# elasticNode.net
KiCad netlist of a schematic drawn in EAGLE
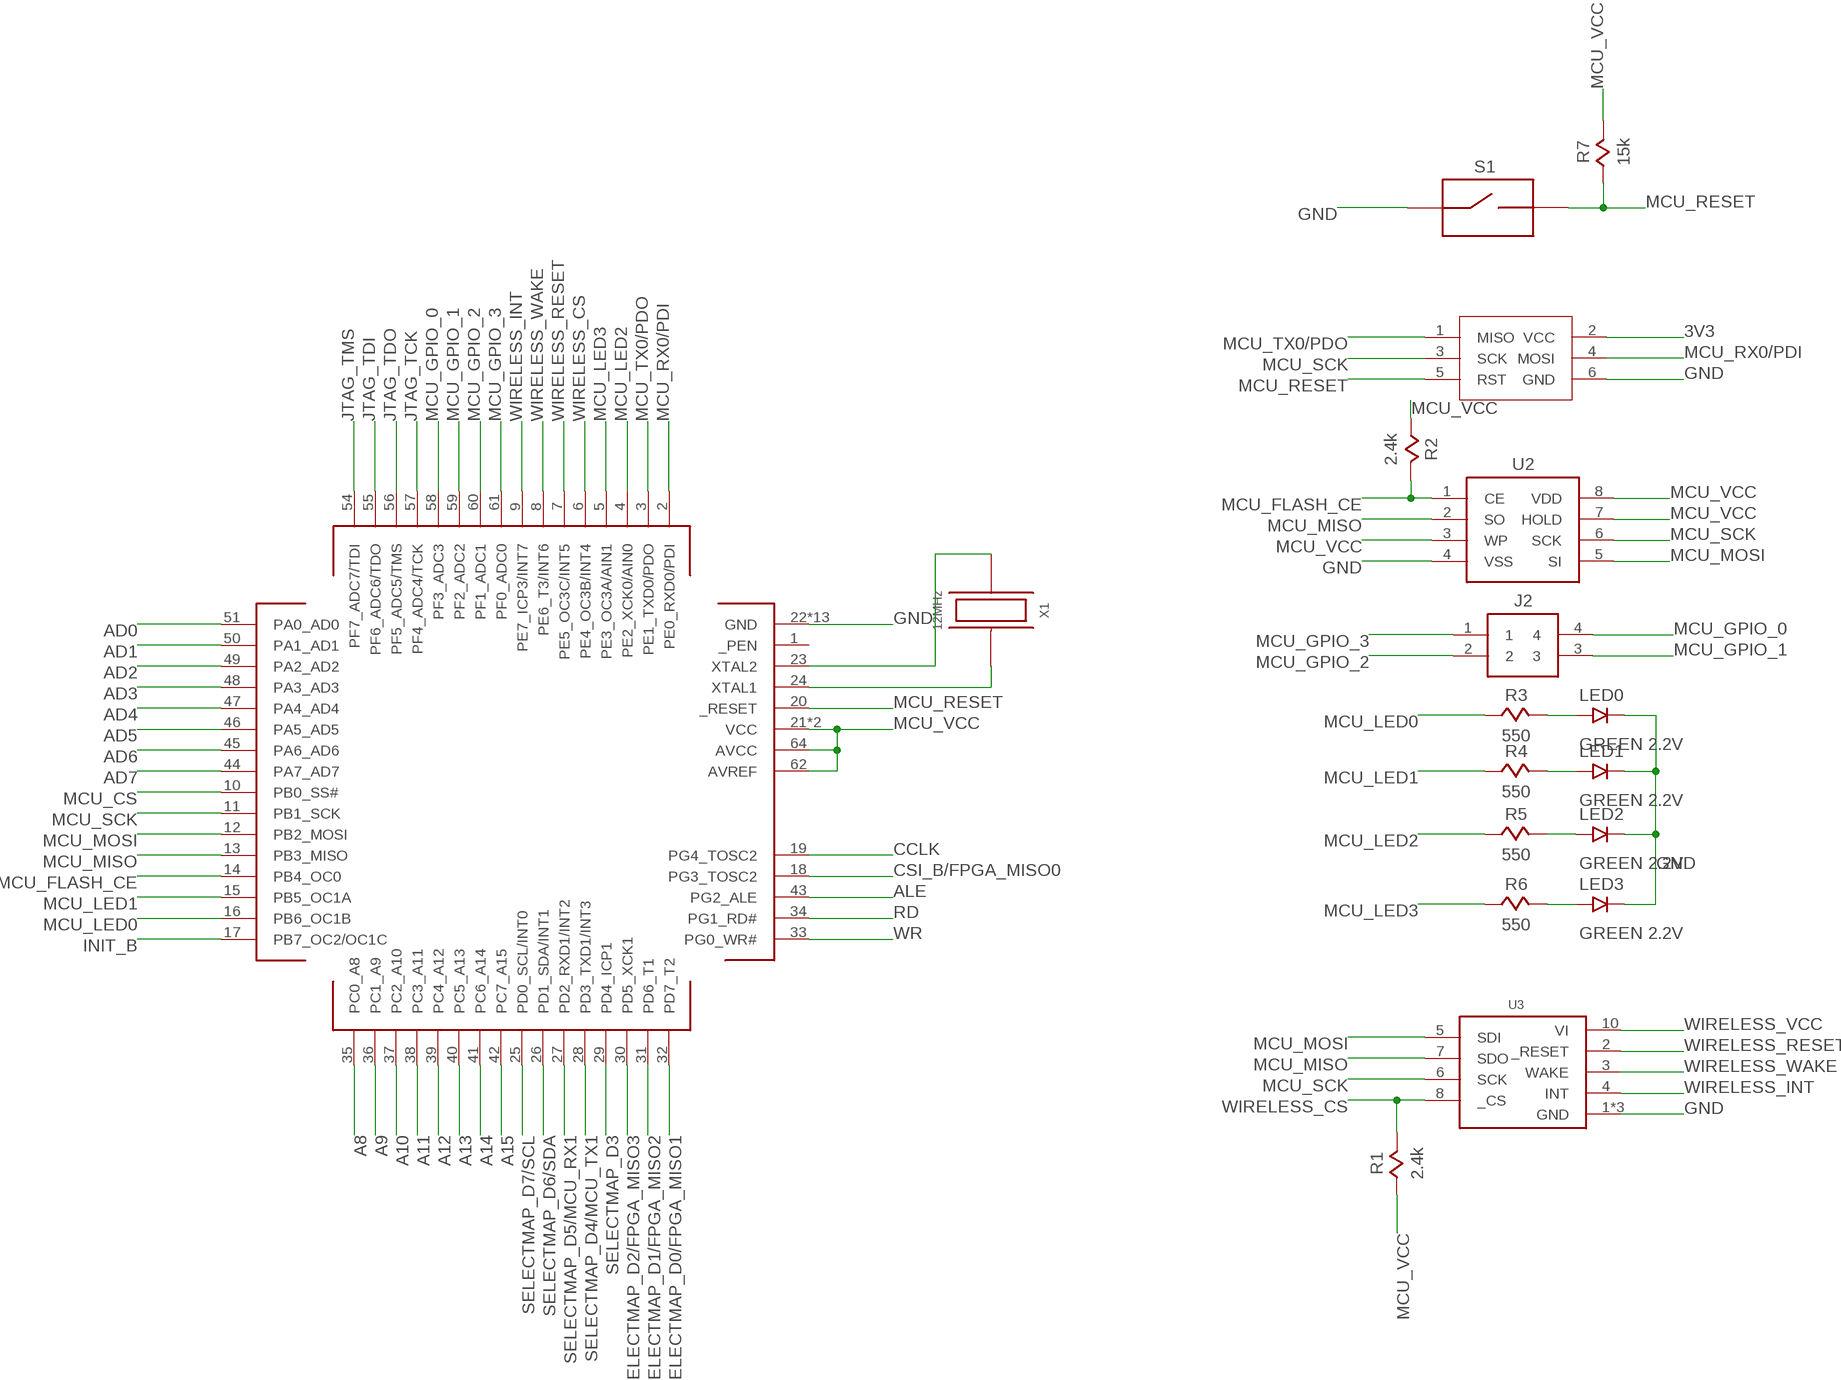
[diagram p0: schematic, sheet 1]
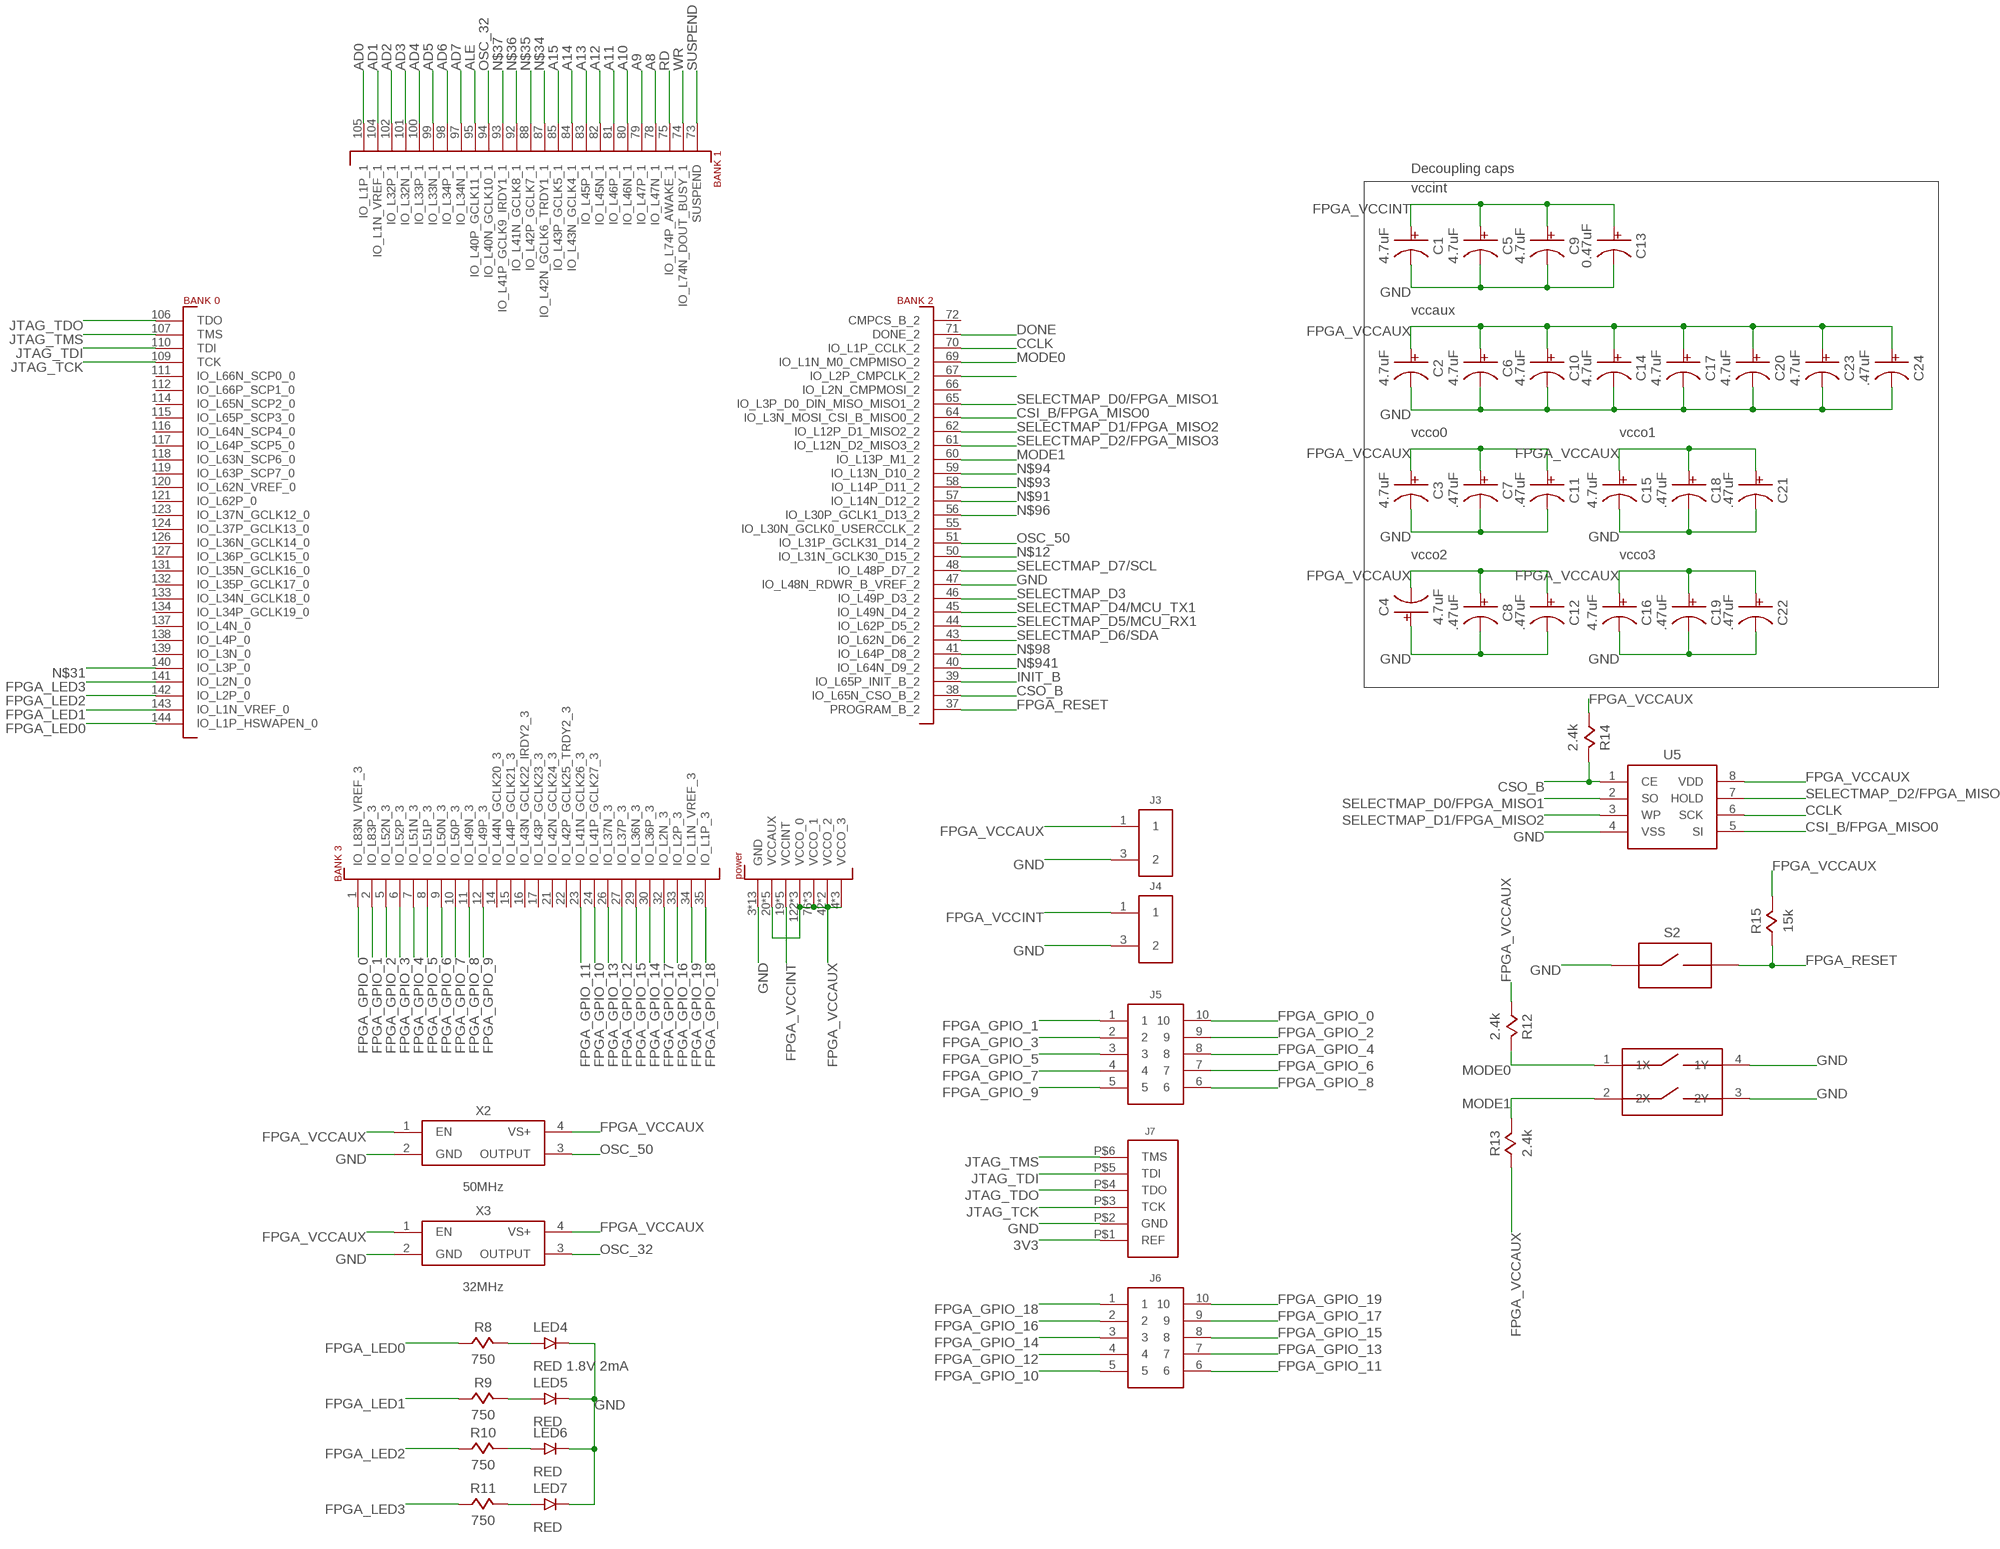
[diagram p1: schematic, sheet 2]
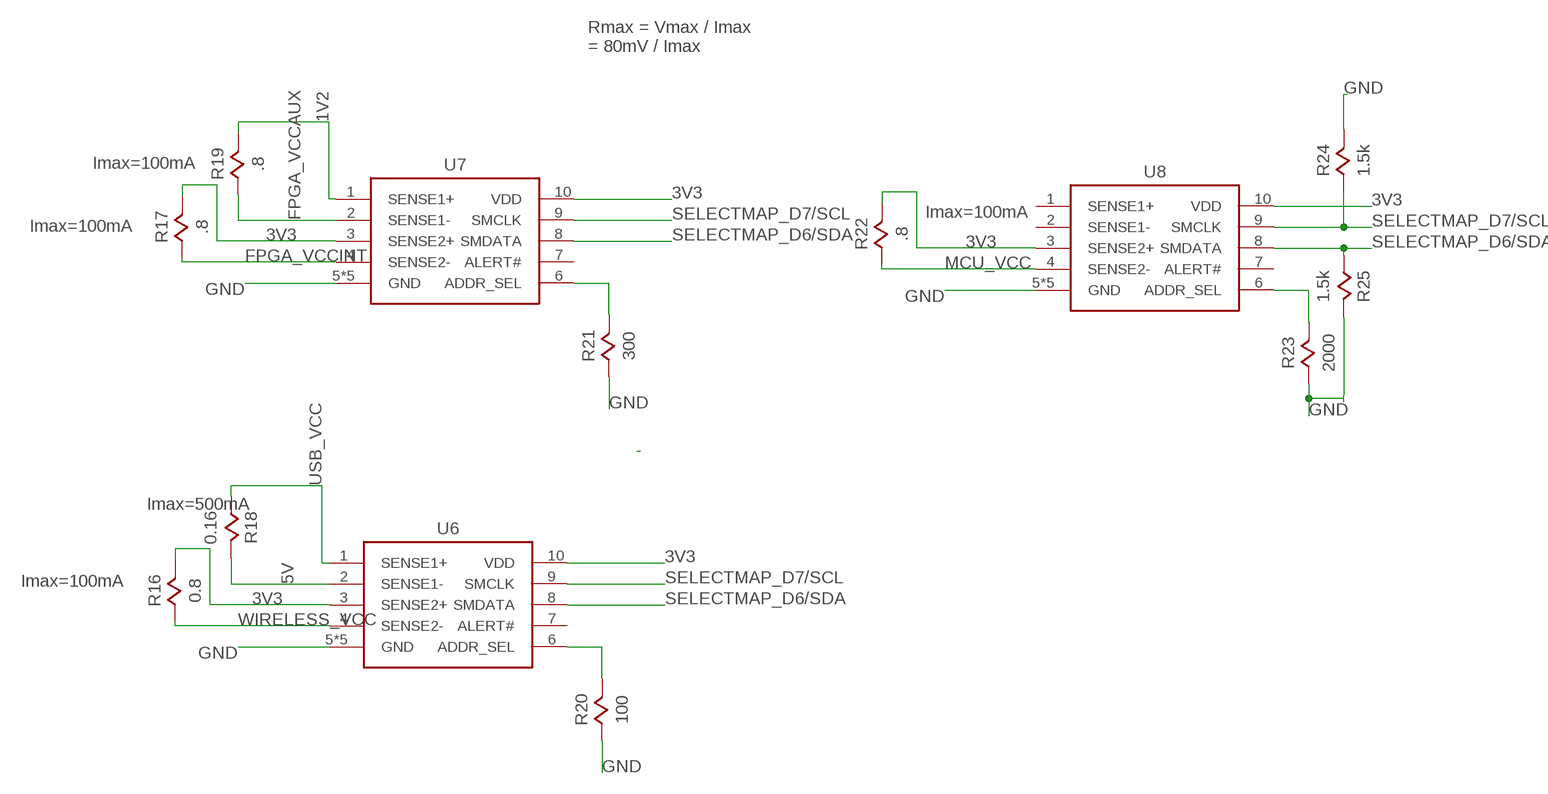
[diagram p2: schematic, sheet 3]
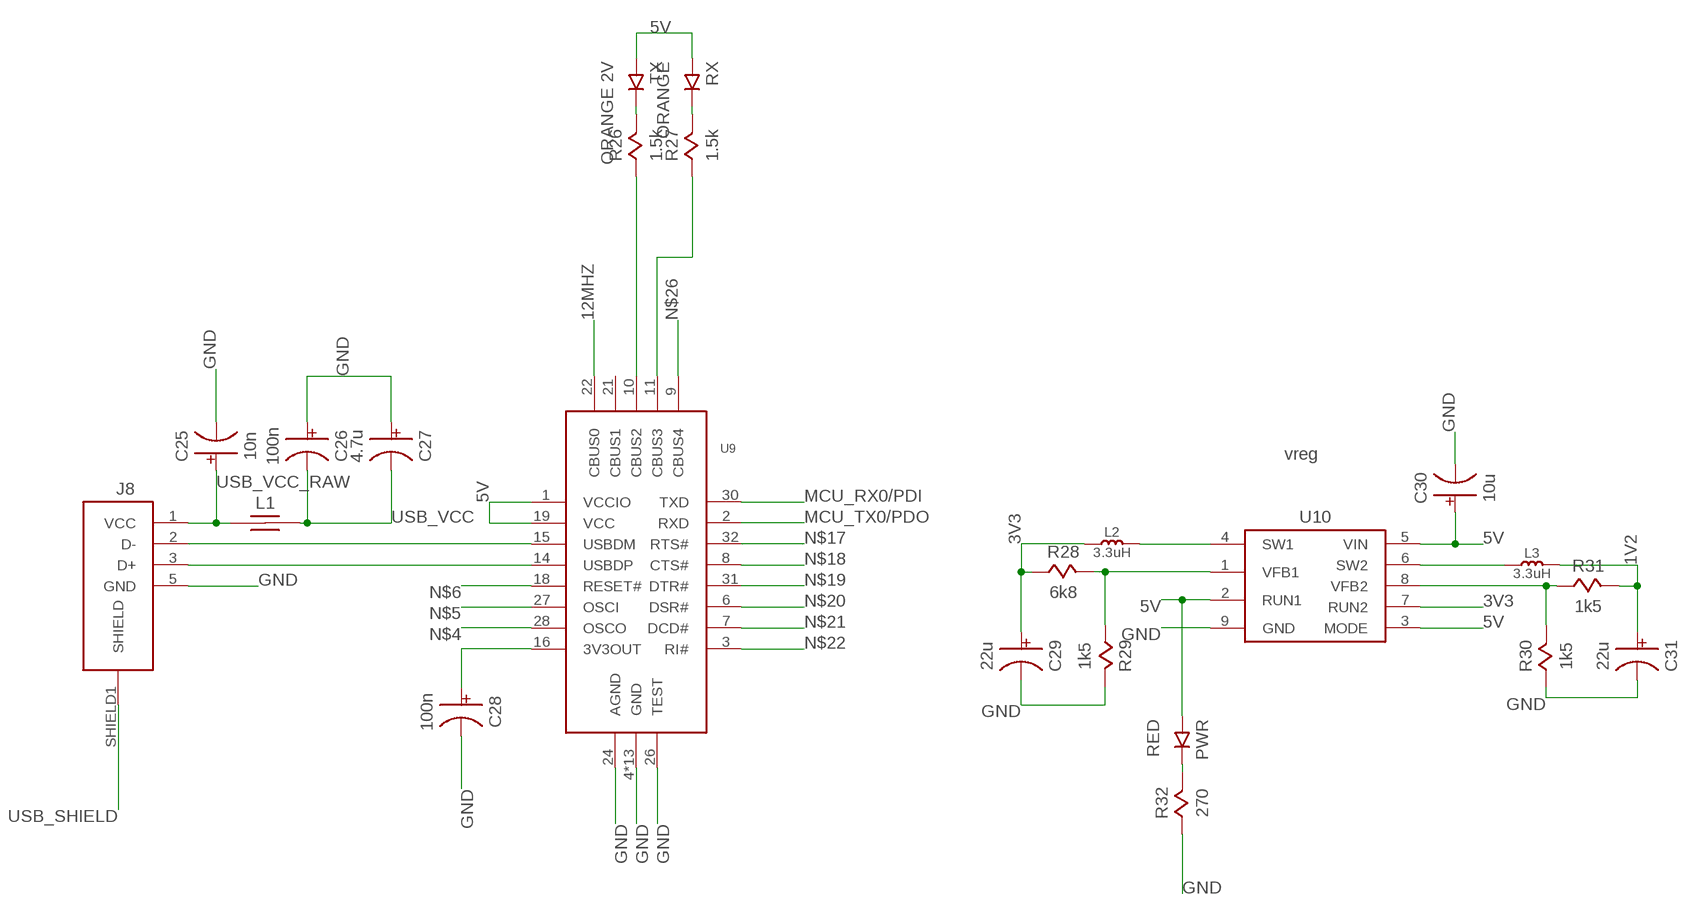
[diagram p3: schematic, sheet 4]

(export (version "E")
  (design (tool "Eeschema 10.0.6"))
  (components
    (comp (ref "C1")
      (value "4.7uF")
      (footprint "eagle-import:0805")
      (libsource (lib "eagle-import") (part "CAPACITOR0805"))
    )
    (comp (ref "C2")
      (value "4.7uF")
      (footprint "eagle-import:0805")
      (libsource (lib "eagle-import") (part "CAPACITOR0805"))
    )
    (comp (ref "C3")
      (value "4.7uF")
      (footprint "eagle-import:0805")
      (libsource (lib "eagle-import") (part "CAPACITOR0805"))
    )
    (comp (ref "C4")
      (value "4.7uF")
      (footprint "eagle-import:0805")
      (libsource (lib "eagle-import") (part "CAPACITOR0805"))
    )
    (comp (ref "C5")
      (value "4.7uF")
      (footprint "eagle-import:0805")
      (libsource (lib "eagle-import") (part "CAPACITOR0805"))
    )
    (comp (ref "C6")
      (value "4.7uF")
      (footprint "eagle-import:0805")
      (libsource (lib "eagle-import") (part "CAPACITOR0805"))
    )
    (comp (ref "C7")
      (value ".47uF")
      (footprint "eagle-import:0402")
      (libsource (lib "eagle-import") (part "CAPACITOR0402"))
    )
    (comp (ref "C8")
      (value ".47uF")
      (footprint "eagle-import:0402")
      (libsource (lib "eagle-import") (part "CAPACITOR0402"))
    )
    (comp (ref "C9")
      (value "4.7uF")
      (footprint "eagle-import:0805")
      (libsource (lib "eagle-import") (part "CAPACITOR0805"))
    )
    (comp (ref "C10")
      (value "4.7uF")
      (footprint "eagle-import:0805")
      (libsource (lib "eagle-import") (part "CAPACITOR0805"))
    )
    (comp (ref "C11")
      (value ".47uF")
      (footprint "eagle-import:0402")
      (libsource (lib "eagle-import") (part "CAPACITOR0402"))
    )
    (comp (ref "C12")
      (value ".47uF")
      (footprint "eagle-import:0402")
      (libsource (lib "eagle-import") (part "CAPACITOR0402"))
    )
    (comp (ref "C13")
      (value "0.47uF")
      (footprint "eagle-import:0402")
      (libsource (lib "eagle-import") (part "CAPACITOR0402"))
    )
    (comp (ref "C14")
      (value "4.7uF")
      (footprint "eagle-import:0805")
      (libsource (lib "eagle-import") (part "CAPACITOR0805"))
    )
    (comp (ref "C15")
      (value "4.7uF")
      (footprint "eagle-import:0805")
      (libsource (lib "eagle-import") (part "CAPACITOR0805"))
    )
    (comp (ref "C16")
      (value "4.7uF")
      (footprint "eagle-import:0805")
      (libsource (lib "eagle-import") (part "CAPACITOR0805"))
    )
    (comp (ref "C17")
      (value "4.7uF")
      (footprint "eagle-import:0805")
      (libsource (lib "eagle-import") (part "CAPACITOR0805"))
    )
    (comp (ref "C18")
      (value ".47uF")
      (footprint "eagle-import:0402")
      (libsource (lib "eagle-import") (part "CAPACITOR0402"))
    )
    (comp (ref "C19")
      (value ".47uF")
      (footprint "eagle-import:0402")
      (libsource (lib "eagle-import") (part "CAPACITOR0402"))
    )
    (comp (ref "C20")
      (value "4.7uF")
      (footprint "eagle-import:0805")
      (libsource (lib "eagle-import") (part "CAPACITOR0805"))
    )
    (comp (ref "C21")
      (value ".47uF")
      (footprint "eagle-import:0402")
      (libsource (lib "eagle-import") (part "CAPACITOR0402"))
    )
    (comp (ref "C22")
      (value ".47uF")
      (footprint "eagle-import:0402")
      (libsource (lib "eagle-import") (part "CAPACITOR0402"))
    )
    (comp (ref "C23")
      (value "4.7uF")
      (footprint "eagle-import:0805")
      (libsource (lib "eagle-import") (part "CAPACITOR0805"))
    )
    (comp (ref "C24")
      (value ".47uF")
      (footprint "eagle-import:0805")
      (libsource (lib "eagle-import") (part "CAPACITOR0805"))
    )
    (comp (ref "J3")
      (value "FEMALE_HEADER_2X1")
      (footprint "eagle-import:2X1_HEADER")
      (libsource (lib "eagle-import") (part "FEMALE_HEADER_2X1"))
    )
    (comp (ref "J4")
      (value "FEMALE_HEADER_2X1")
      (footprint "eagle-import:2X1_HEADER")
      (libsource (lib "eagle-import") (part "FEMALE_HEADER_2X1"))
    )
    (comp (ref "J5")
      (value "FEMALE_HEADER_5X2")
      (footprint "eagle-import:5X2_HEADER")
      (libsource (lib "eagle-import") (part "FEMALE_HEADER_5X2"))
    )
    (comp (ref "J6")
      (value "FEMALE_HEADER_5X2")
      (footprint "eagle-import:5X2_HEADER")
      (libsource (lib "eagle-import") (part "FEMALE_HEADER_5X2"))
    )
    (comp (ref "J7")
      (value "JTAG_CONN_6PINTHT")
      (footprint "eagle-import:6X1_HEADER")
      (libsource (lib "eagle-import") (part "JTAG_CONN_6PINTHT"))
    )
    (comp (ref "LED4")
      (value "RED 1.8V 2mA")
      (footprint "eagle-import:0805")
      (libsource (lib "eagle-import") (part "LED"))
    )
    (comp (ref "LED5")
      (value "RED")
      (footprint "eagle-import:0805")
      (libsource (lib "eagle-import") (part "LED"))
    )
    (comp (ref "LED6")
      (value "RED")
      (footprint "eagle-import:0805")
      (libsource (lib "eagle-import") (part "LED"))
    )
    (comp (ref "LED7")
      (value "RED")
      (footprint "eagle-import:0805")
      (libsource (lib "eagle-import") (part "LED"))
    )
    (comp (ref "R8")
      (value "750")
      (footprint "eagle-import:0805")
      (libsource (lib "eagle-import") (part "RESISTOR"))
    )
    (comp (ref "R9")
      (value "750")
      (footprint "eagle-import:0805")
      (libsource (lib "eagle-import") (part "RESISTOR"))
    )
    (comp (ref "R10")
      (value "750")
      (footprint "eagle-import:0805")
      (libsource (lib "eagle-import") (part "RESISTOR"))
    )
    (comp (ref "R11")
      (value "750")
      (footprint "eagle-import:0805")
      (libsource (lib "eagle-import") (part "RESISTOR"))
    )
    (comp (ref "R12")
      (value "2.4k")
      (footprint "eagle-import:0805")
      (libsource (lib "eagle-import") (part "RESISTOR"))
    )
    (comp (ref "R13")
      (value "2.4k")
      (footprint "eagle-import:0805")
      (libsource (lib "eagle-import") (part "RESISTOR"))
    )
    (comp (ref "R14")
      (value "2.4k")
      (footprint "eagle-import:0805")
      (libsource (lib "eagle-import") (part "RESISTOR"))
    )
    (comp (ref "R15")
      (value "15k")
      (footprint "eagle-import:0805")
      (libsource (lib "eagle-import") (part "RESISTOR"))
    )
    (comp (ref "S2")
      (value "SPST_BUTTON2PIN_SMT")
      (footprint "eagle-import:SPST_2PIN_SMT")
      (libsource (lib "eagle-import") (part "SPST_BUTTON2PIN_SMT"))
    )
    (comp (ref "S3")
      (value "SPST_DIP_2SMT")
      (footprint "eagle-import:SPST_DIP2_SMT")
      (libsource (lib "eagle-import") (part "SPST_DIP_2SMT"))
    )
    (comp (ref "U4")
      (value "SPARTAN6-LX9")
      (footprint "eagle-import:TQG144")
      (libsource (lib "eagle-import") (part "SPARTAN6-LX9"))
    )
    (comp (ref "U5")
      (value "SST26VF032B")
      (footprint "eagle-import:SOIC8")
      (libsource (lib "eagle-import") (part "SST26VF032B"))
    )
    (comp (ref "X2")
      (value "50MHz")
      (footprint "eagle-import:3.2X2.5_OSC")
      (libsource (lib "eagle-import") (part "OSCILLATOR3.2X2.5"))
    )
    (comp (ref "X3")
      (value "32MHz")
      (footprint "eagle-import:3.2X2.5_OSC")
      (libsource (lib "eagle-import") (part "OSCILLATOR3.2X2.5"))
    )
    (comp (ref "C25")
      (value "10n")
      (footprint "eagle-import:0805")
      (libsource (lib "eagle-import") (part "CAPACITOR0805"))
    )
    (comp (ref "C26")
      (value "100n")
      (footprint "eagle-import:0805")
      (libsource (lib "eagle-import") (part "CAPACITOR0805"))
    )
    (comp (ref "C27")
      (value "4.7u")
      (footprint "eagle-import:0805")
      (libsource (lib "eagle-import") (part "CAPACITOR0805"))
    )
    (comp (ref "C28")
      (value "100n")
      (footprint "eagle-import:0805")
      (libsource (lib "eagle-import") (part "CAPACITOR0805"))
    )
    (comp (ref "C29")
      (value "22u")
      (footprint "eagle-import:0805")
      (libsource (lib "eagle-import") (part "CAPACITOR0805"))
    )
    (comp (ref "C30")
      (value "10u")
      (footprint "eagle-import:0805")
      (libsource (lib "eagle-import") (part "CAPACITOR0805"))
    )
    (comp (ref "C31")
      (value "22u")
      (footprint "eagle-import:0805")
      (libsource (lib "eagle-import") (part "CAPACITOR0805"))
    )
    (comp (ref "J8")
      (value "USB_CONN")
      (footprint "eagle-import:USB_MICRO_B")
      (libsource (lib "eagle-import") (part "USB_CONN"))
    )
    (comp (ref "L1")
      (value "40Ohm 1.5A")
      (footprint "eagle-import:0805")
      (libsource (lib "eagle-import") (part "FERRITE_BEAD"))
    )
    (comp (ref "L2")
      (value "3.3uH")
      (footprint "eagle-import:0805")
      (libsource (lib "eagle-import") (part "INDUCTOR"))
    )
    (comp (ref "L3")
      (value "3.3uH")
      (footprint "eagle-import:0805")
      (libsource (lib "eagle-import") (part "INDUCTOR"))
    )
    (comp (ref "PWR")
      (value "RED")
      (footprint "eagle-import:0805")
      (libsource (lib "eagle-import") (part "LED"))
    )
    (comp (ref "R26")
      (value "1.5k")
      (footprint "eagle-import:0805")
      (libsource (lib "eagle-import") (part "RESISTOR"))
    )
    (comp (ref "R27")
      (value "1.5k")
      (footprint "eagle-import:0805")
      (libsource (lib "eagle-import") (part "RESISTOR"))
    )
    (comp (ref "R28")
      (value "6k8")
      (footprint "eagle-import:0805")
      (libsource (lib "eagle-import") (part "RESISTOR"))
    )
    (comp (ref "R29")
      (value "1k5")
      (footprint "eagle-import:0805")
      (libsource (lib "eagle-import") (part "RESISTOR"))
    )
    (comp (ref "R30")
      (value "1k5")
      (footprint "eagle-import:0805")
      (libsource (lib "eagle-import") (part "RESISTOR"))
    )
    (comp (ref "R31")
      (value "1k5")
      (footprint "eagle-import:0805")
      (libsource (lib "eagle-import") (part "RESISTOR"))
    )
    (comp (ref "R32")
      (value "270")
      (footprint "eagle-import:0805")
      (libsource (lib "eagle-import") (part "RESISTOR"))
    )
    (comp (ref "RX")
      (value "ORANGE")
      (footprint "eagle-import:0805")
      (libsource (lib "eagle-import") (part "LED"))
    )
    (comp (ref "TX")
      (value "ORANGE 2V")
      (footprint "eagle-import:0805")
      (libsource (lib "eagle-import") (part "LED"))
    )
    (comp (ref "U9")
      (value "FT232R")
      (footprint "eagle-import:QFN32")
      (libsource (lib "eagle-import") (part "FT232R"))
    )
    (comp (ref "U10")
      (value "LTC3419DFN")
      (footprint "eagle-import:DFN8")
      (libsource (lib "eagle-import") (part "LTC3419DFN"))
    )
    (comp (ref "R16")
      (value "0.8")
      (footprint "eagle-import:0805")
      (libsource (lib "eagle-import") (part "RESISTOR"))
    )
    (comp (ref "R17")
      (value ".8")
      (footprint "eagle-import:0805")
      (libsource (lib "eagle-import") (part "RESISTOR"))
    )
    (comp (ref "R18")
      (value "0.16")
      (footprint "eagle-import:0805")
      (libsource (lib "eagle-import") (part "RESISTOR"))
    )
    (comp (ref "R19")
      (value ".8")
      (footprint "eagle-import:0805")
      (libsource (lib "eagle-import") (part "RESISTOR"))
    )
    (comp (ref "R20")
      (value "100")
      (footprint "eagle-import:0805")
      (libsource (lib "eagle-import") (part "RESISTOR"))
    )
    (comp (ref "R21")
      (value "300")
      (footprint "eagle-import:0805")
      (libsource (lib "eagle-import") (part "RESISTOR"))
    )
    (comp (ref "R22")
      (value ".8")
      (footprint "eagle-import:0805")
      (libsource (lib "eagle-import") (part "RESISTOR"))
    )
    (comp (ref "R23")
      (value "2000")
      (footprint "eagle-import:0805")
      (libsource (lib "eagle-import") (part "RESISTOR"))
    )
    (comp (ref "R24")
      (value "1.5k")
      (footprint "eagle-import:0805")
      (libsource (lib "eagle-import") (part "RESISTOR"))
    )
    (comp (ref "R25")
      (value "1.5k")
      (footprint "eagle-import:0805")
      (libsource (lib "eagle-import") (part "RESISTOR"))
    )
    (comp (ref "U6")
      (value "PAC1720")
      (footprint "eagle-import:VDFN10")
      (libsource (lib "eagle-import") (part "PAC1720"))
    )
    (comp (ref "U7")
      (value "PAC1720")
      (footprint "eagle-import:VDFN10")
      (libsource (lib "eagle-import") (part "PAC1720"))
    )
    (comp (ref "U8")
      (value "PAC1720")
      (footprint "eagle-import:VDFN10")
      (libsource (lib "eagle-import") (part "PAC1720"))
    )
    (comp (ref "J1")
      (value "ISP_CONN_6PIN")
      (footprint "eagle-import:3X2_HEADER_SMT")
      (libsource (lib "eagle-import") (part "ISP_CONN_6PIN"))
    )
    (comp (ref "J2")
      (value "FEMALE_HEADER_2X2")
      (footprint "eagle-import:2X2_HEADER")
      (libsource (lib "eagle-import") (part "FEMALE_HEADER_2X2"))
    )
    (comp (ref "LED0")
      (value "GREEN 2.2V")
      (footprint "eagle-import:0805")
      (libsource (lib "eagle-import") (part "LED"))
    )
    (comp (ref "LED1")
      (value "GREEN 2.2V")
      (footprint "eagle-import:0805")
      (libsource (lib "eagle-import") (part "LED"))
    )
    (comp (ref "LED2")
      (value "GREEN 2.2V")
      (footprint "eagle-import:0805")
      (libsource (lib "eagle-import") (part "LED"))
    )
    (comp (ref "LED3")
      (value "GREEN 2.2V")
      (footprint "eagle-import:0805")
      (libsource (lib "eagle-import") (part "LED"))
    )
    (comp (ref "R1")
      (value "2.4k")
      (footprint "eagle-import:0805")
      (libsource (lib "eagle-import") (part "RESISTOR"))
    )
    (comp (ref "R2")
      (value "2.4k")
      (footprint "eagle-import:0805")
      (libsource (lib "eagle-import") (part "RESISTOR"))
    )
    (comp (ref "R3")
      (value "550")
      (footprint "eagle-import:0805")
      (libsource (lib "eagle-import") (part "RESISTOR"))
    )
    (comp (ref "R4")
      (value "550")
      (footprint "eagle-import:0805")
      (libsource (lib "eagle-import") (part "RESISTOR"))
    )
    (comp (ref "R5")
      (value "550")
      (footprint "eagle-import:0805")
      (libsource (lib "eagle-import") (part "RESISTOR"))
    )
    (comp (ref "R6")
      (value "550")
      (footprint "eagle-import:0805")
      (libsource (lib "eagle-import") (part "RESISTOR"))
    )
    (comp (ref "R7")
      (value "15k")
      (footprint "eagle-import:0805")
      (libsource (lib "eagle-import") (part "RESISTOR"))
    )
    (comp (ref "S1")
      (value "SPST_BUTTON2PIN_SMT")
      (footprint "eagle-import:SPST_2PIN_SMT")
      (libsource (lib "eagle-import") (part "SPST_BUTTON2PIN_SMT"))
    )
    (comp (ref "U1")
      (value "ATMEGA64AQFN")
      (footprint "eagle-import:QFN64")
      (libsource (lib "eagle-import") (part "ATMEGA64AQFN"))
    )
    (comp (ref "U2")
      (value "SST26VF032B")
      (footprint "eagle-import:SOIC8")
      (libsource (lib "eagle-import") (part "SST26VF032B"))
    )
    (comp (ref "U3")
      (value "MRF24J40MA")
      (footprint "eagle-import:MRF24J40MA")
      (libsource (lib "eagle-import") (part "MRF24J40MA"))
    )
    (comp (ref "X1")
      (value "12MHz")
      (footprint "eagle-import:3.2X2.5_OSC")
      (libsource (lib "eagle-import") (part "QUARTZ"))
    )
  )
  (nets
    (net (code "1") (name "1V2") (class "Default")
      (node (ref "C31") (pin "1") (pinfunction "P$1_1") (pintype "bidirectional"))
      (node (ref "L3") (pin "2") (pinfunction "P$2_2") (pintype "bidirectional"))
      (node (ref "R19") (pin "2") (pinfunction "2_2") (pintype "bidirectional"))
      (node (ref "R31") (pin "2") (pinfunction "2_2") (pintype "bidirectional"))
      (node (ref "U7") (pin "1") (pinfunction "SENSE1+_1") (pintype "bidirectional"))
    )
    (net (code "2") (name "3V3") (class "Default")
      (node (ref "C29") (pin "1") (pinfunction "P$1_1") (pintype "bidirectional"))
      (node (ref "J1") (pin "2") (pinfunction "VCC_2") (pintype "bidirectional"))
      (node (ref "J7") (pin "P$1") (pinfunction "REF_P$1") (pintype "bidirectional"))
      (node (ref "L2") (pin "1") (pinfunction "P$1_1") (pintype "bidirectional"))
      (node (ref "R16") (pin "2") (pinfunction "2_2") (pintype "bidirectional"))
      (node (ref "R17") (pin "2") (pinfunction "2_2") (pintype "bidirectional"))
      (node (ref "R22") (pin "2") (pinfunction "2_2") (pintype "bidirectional"))
      (node (ref "R28") (pin "1") (pinfunction "1_1") (pintype "bidirectional"))
      (node (ref "U10") (pin "7") (pinfunction "RUN2_7") (pintype "bidirectional"))
      (node (ref "U6") (pin "10") (pinfunction "VDD_10") (pintype "bidirectional"))
      (node (ref "U6") (pin "3") (pinfunction "SENSE2+_3") (pintype "bidirectional"))
      (node (ref "U7") (pin "10") (pinfunction "VDD_10") (pintype "bidirectional"))
      (node (ref "U7") (pin "3") (pinfunction "SENSE2+_3") (pintype "bidirectional"))
      (node (ref "U8") (pin "10") (pinfunction "VDD_10") (pintype "bidirectional"))
      (node (ref "U8") (pin "3") (pinfunction "SENSE2+_3") (pintype "bidirectional"))
    )
    (net (code "3") (name "5V") (class "Default")
      (node (ref "C30") (pin "1") (pinfunction "P$1_1") (pintype "bidirectional"))
      (node (ref "PWR") (pin "1") (pinfunction "1_1") (pintype "bidirectional"))
      (node (ref "R18") (pin "2") (pinfunction "2_2") (pintype "bidirectional"))
      (node (ref "RX") (pin "1") (pinfunction "1_1") (pintype "bidirectional"))
      (node (ref "TX") (pin "1") (pinfunction "1_1") (pintype "bidirectional"))
      (node (ref "U10") (pin "2") (pinfunction "RUN1_2") (pintype "bidirectional"))
      (node (ref "U10") (pin "3") (pinfunction "MODE_3") (pintype "bidirectional"))
      (node (ref "U10") (pin "5") (pinfunction "VIN_5") (pintype "bidirectional"))
      (node (ref "U6") (pin "2") (pinfunction "SENSE1-_2") (pintype "bidirectional"))
      (node (ref "U9") (pin "1") (pinfunction "VCCIO_1") (pintype "bidirectional"))
      (node (ref "U9") (pin "19") (pinfunction "VCC_19") (pintype "bidirectional"))
    )
    (net (code "4") (name "12MHZ") (class "Default")
      (node (ref "U9") (pin "22") (pinfunction "CBUS0_22") (pintype "bidirectional"))
    )
    (net (code "5") (name "A8") (class "Default")
      (node (ref "U1") (pin "35") (pinfunction "PC0_A8_35") (pintype "bidirectional"))
      (node (ref "U4") (pin "78") (pinfunction "IO_L47N_1_78") (pintype "bidirectional"))
    )
    (net (code "6") (name "A9") (class "Default")
      (node (ref "U1") (pin "36") (pinfunction "PC1_A9_36") (pintype "bidirectional"))
      (node (ref "U4") (pin "79") (pinfunction "IO_L47P_1_79") (pintype "bidirectional"))
    )
    (net (code "7") (name "A10") (class "Default")
      (node (ref "U1") (pin "37") (pinfunction "PC2_A10_37") (pintype "bidirectional"))
      (node (ref "U4") (pin "80") (pinfunction "IO_L46N_1_80") (pintype "bidirectional"))
    )
    (net (code "8") (name "A11") (class "Default")
      (node (ref "U1") (pin "38") (pinfunction "PC3_A11_38") (pintype "bidirectional"))
      (node (ref "U4") (pin "81") (pinfunction "IO_L46P_1_81") (pintype "bidirectional"))
    )
    (net (code "9") (name "A12") (class "Default")
      (node (ref "U1") (pin "39") (pinfunction "PC4_A12_39") (pintype "bidirectional"))
      (node (ref "U4") (pin "82") (pinfunction "IO_L45N_1_82") (pintype "bidirectional"))
    )
    (net (code "10") (name "A13") (class "Default")
      (node (ref "U1") (pin "40") (pinfunction "PC5_A13_40") (pintype "bidirectional"))
      (node (ref "U4") (pin "83") (pinfunction "IO_L45P_1_83") (pintype "bidirectional"))
    )
    (net (code "11") (name "A14") (class "Default")
      (node (ref "U1") (pin "41") (pinfunction "PC6_A14_41") (pintype "bidirectional"))
      (node (ref "U4") (pin "84") (pinfunction "IO_L43N_GCLK4_1_84") (pintype "bidirectional"))
    )
    (net (code "12") (name "A15") (class "Default")
      (node (ref "U1") (pin "42") (pinfunction "PC7_A15_42") (pintype "bidirectional"))
      (node (ref "U4") (pin "85") (pinfunction "IO_L43P_GCLK5_1_85") (pintype "bidirectional"))
    )
    (net (code "13") (name "AD0") (class "Default")
      (node (ref "U1") (pin "51") (pinfunction "PA0_AD0_51") (pintype "bidirectional"))
      (node (ref "U4") (pin "105") (pinfunction "IO_L1P_1_105") (pintype "bidirectional"))
    )
    (net (code "14") (name "AD1") (class "Default")
      (node (ref "U1") (pin "50") (pinfunction "PA1_AD1_50") (pintype "bidirectional"))
      (node (ref "U4") (pin "104") (pinfunction "IO_L1N_VREF_1_104") (pintype "bidirectional"))
    )
    (net (code "15") (name "AD2") (class "Default")
      (node (ref "U1") (pin "49") (pinfunction "PA2_AD2_49") (pintype "bidirectional"))
      (node (ref "U4") (pin "102") (pinfunction "IO_L32P_1_102") (pintype "bidirectional"))
    )
    (net (code "16") (name "AD3") (class "Default")
      (node (ref "U1") (pin "48") (pinfunction "PA3_AD3_48") (pintype "bidirectional"))
      (node (ref "U4") (pin "101") (pinfunction "IO_L32N_1_101") (pintype "bidirectional"))
    )
    (net (code "17") (name "AD4") (class "Default")
      (node (ref "U1") (pin "47") (pinfunction "PA4_AD4_47") (pintype "bidirectional"))
      (node (ref "U4") (pin "100") (pinfunction "IO_L33P_1_100") (pintype "bidirectional"))
    )
    (net (code "18") (name "AD5") (class "Default")
      (node (ref "U1") (pin "46") (pinfunction "PA5_AD5_46") (pintype "bidirectional"))
      (node (ref "U4") (pin "99") (pinfunction "IO_L33N_1_99") (pintype "bidirectional"))
    )
    (net (code "19") (name "AD6") (class "Default")
      (node (ref "U1") (pin "45") (pinfunction "PA6_AD6_45") (pintype "bidirectional"))
      (node (ref "U4") (pin "98") (pinfunction "IO_L34P_1_98") (pintype "bidirectional"))
    )
    (net (code "20") (name "AD7") (class "Default")
      (node (ref "U1") (pin "44") (pinfunction "PA7_AD7_44") (pintype "bidirectional"))
      (node (ref "U4") (pin "97") (pinfunction "IO_L34N_1_97") (pintype "bidirectional"))
    )
    (net (code "21") (name "ALE") (class "Default")
      (node (ref "U1") (pin "43") (pinfunction "PG2_ALE_43") (pintype "bidirectional"))
      (node (ref "U4") (pin "95") (pinfunction "IO_L40P_GCLK11_1_95") (pintype "bidirectional"))
    )
    (net (code "22") (name "CCLK") (class "Default")
      (node (ref "U1") (pin "19") (pinfunction "PG4_TOSC2_19") (pintype "bidirectional"))
      (node (ref "U4") (pin "70") (pinfunction "IO_L1P_CCLK_2_70") (pintype "bidirectional"))
      (node (ref "U5") (pin "6") (pinfunction "SCK_6") (pintype "bidirectional"))
    )
    (net (code "23") (name "CSI_B{slash}FPGA_MISO0") (class "Default")
      (node (ref "U1") (pin "18") (pinfunction "PG3_TOSC2_18") (pintype "bidirectional"))
      (node (ref "U4") (pin "64") (pinfunction "IO_L3N_MOSI_CSI_B_MISO0_2_64") (pintype "bidirectional"))
      (node (ref "U5") (pin "5") (pinfunction "SI_5") (pintype "bidirectional"))
    )
    (net (code "24") (name "CSO_B") (class "Default")
      (node (ref "R14") (pin "2") (pinfunction "2_2") (pintype "bidirectional"))
      (node (ref "U4") (pin "38") (pinfunction "IO_L65N_CSO_B_2_38") (pintype "bidirectional"))
      (node (ref "U5") (pin "1") (pinfunction "CE_1") (pintype "bidirectional"))
    )
    (net (code "25") (name "DONE") (class "Default")
      (node (ref "U4") (pin "71") (pinfunction "DONE_2_71") (pintype "bidirectional"))
    )
    (net (code "26") (name "FPGA_GPIO_0") (class "Default")
      (node (ref "J5") (pin "10") (pinfunction "10_10") (pintype "bidirectional"))
      (node (ref "U4") (pin "1") (pinfunction "IO_L83N_VREF_3_1") (pintype "bidirectional"))
    )
    (net (code "27") (name "FPGA_GPIO_1") (class "Default")
      (node (ref "J5") (pin "1") (pinfunction "1_1") (pintype "bidirectional"))
      (node (ref "U4") (pin "2") (pinfunction "IO_L83P_3_2") (pintype "bidirectional"))
    )
    (net (code "28") (name "FPGA_GPIO_2") (class "Default")
      (node (ref "J5") (pin "9") (pinfunction "9_9") (pintype "bidirectional"))
      (node (ref "U4") (pin "5") (pinfunction "IO_L52N_3_5") (pintype "bidirectional"))
    )
    (net (code "29") (name "FPGA_GPIO_3") (class "Default")
      (node (ref "J5") (pin "2") (pinfunction "2_2") (pintype "bidirectional"))
      (node (ref "U4") (pin "6") (pinfunction "IO_L52P_3_6") (pintype "bidirectional"))
    )
    (net (code "30") (name "FPGA_GPIO_4") (class "Default")
      (node (ref "J5") (pin "8") (pinfunction "8_8") (pintype "bidirectional"))
      (node (ref "U4") (pin "7") (pinfunction "IO_L51N_3_7") (pintype "bidirectional"))
    )
    (net (code "31") (name "FPGA_GPIO_5") (class "Default")
      (node (ref "J5") (pin "3") (pinfunction "3_3") (pintype "bidirectional"))
      (node (ref "U4") (pin "8") (pinfunction "IO_L51P_3_8") (pintype "bidirectional"))
    )
    (net (code "32") (name "FPGA_GPIO_6") (class "Default")
      (node (ref "J5") (pin "7") (pinfunction "7_7") (pintype "bidirectional"))
      (node (ref "U4") (pin "9") (pinfunction "IO_L50N_3_9") (pintype "bidirectional"))
    )
    (net (code "33") (name "FPGA_GPIO_7") (class "Default")
      (node (ref "J5") (pin "4") (pinfunction "4_4") (pintype "bidirectional"))
      (node (ref "U4") (pin "10") (pinfunction "IO_L50P_3_10") (pintype "bidirectional"))
    )
    (net (code "34") (name "FPGA_GPIO_8") (class "Default")
      (node (ref "J5") (pin "6") (pinfunction "6_6") (pintype "bidirectional"))
      (node (ref "U4") (pin "11") (pinfunction "IO_L49N_3_11") (pintype "bidirectional"))
    )
    (net (code "35") (name "FPGA_GPIO_9") (class "Default")
      (node (ref "J5") (pin "5") (pinfunction "5_5") (pintype "bidirectional"))
      (node (ref "U4") (pin "12") (pinfunction "IO_L49P_3_12") (pintype "bidirectional"))
    )
    (net (code "36") (name "FPGA_GPIO_10") (class "Default")
      (node (ref "J6") (pin "5") (pinfunction "5_5") (pintype "bidirectional"))
      (node (ref "U4") (pin "24") (pinfunction "IO_L41P_GCLK27_3_24") (pintype "bidirectional"))
    )
    (net (code "37") (name "FPGA_GPIO_11") (class "Default")
      (node (ref "J6") (pin "6") (pinfunction "6_6") (pintype "bidirectional"))
      (node (ref "U4") (pin "23") (pinfunction "IO_L41N_GCLK26_3_23") (pintype "bidirectional"))
    )
    (net (code "38") (name "FPGA_GPIO_12") (class "Default")
      (node (ref "J6") (pin "4") (pinfunction "4_4") (pintype "bidirectional"))
      (node (ref "U4") (pin "27") (pinfunction "IO_L37P_3_27") (pintype "bidirectional"))
    )
    (net (code "39") (name "FPGA_GPIO_13") (class "Default")
      (node (ref "J6") (pin "7") (pinfunction "7_7") (pintype "bidirectional"))
      (node (ref "U4") (pin "26") (pinfunction "IO_L37N_3_26") (pintype "bidirectional"))
    )
    (net (code "40") (name "FPGA_GPIO_14") (class "Default")
      (node (ref "J6") (pin "3") (pinfunction "3_3") (pintype "bidirectional"))
      (node (ref "U4") (pin "30") (pinfunction "IO_L36P_3_30") (pintype "bidirectional"))
    )
    (net (code "41") (name "FPGA_GPIO_15") (class "Default")
      (node (ref "J6") (pin "8") (pinfunction "8_8") (pintype "bidirectional"))
      (node (ref "U4") (pin "29") (pinfunction "IO_L36N_3_29") (pintype "bidirectional"))
    )
    (net (code "42") (name "FPGA_GPIO_16") (class "Default")
      (node (ref "J6") (pin "2") (pinfunction "2_2") (pintype "bidirectional"))
      (node (ref "U4") (pin "33") (pinfunction "IO_L2P_3_33") (pintype "bidirectional"))
    )
    (net (code "43") (name "FPGA_GPIO_17") (class "Default")
      (node (ref "J6") (pin "9") (pinfunction "9_9") (pintype "bidirectional"))
      (node (ref "U4") (pin "32") (pinfunction "IO_L2N_3_32") (pintype "bidirectional"))
    )
    (net (code "44") (name "FPGA_GPIO_18") (class "Default")
      (node (ref "J6") (pin "1") (pinfunction "1_1") (pintype "bidirectional"))
      (node (ref "U4") (pin "35") (pinfunction "IO_L1P_3_35") (pintype "bidirectional"))
    )
    (net (code "45") (name "FPGA_GPIO_19") (class "Default")
      (node (ref "J6") (pin "10") (pinfunction "10_10") (pintype "bidirectional"))
      (node (ref "U4") (pin "34") (pinfunction "IO_L1N_VREF_3_34") (pintype "bidirectional"))
    )
    (net (code "46") (name "FPGA_LED0") (class "Default")
      (node (ref "R8") (pin "1") (pinfunction "1_1") (pintype "bidirectional"))
      (node (ref "U4") (pin "144") (pinfunction "IO_L1P_HSWAPEN_0_144") (pintype "bidirectional"))
    )
    (net (code "47") (name "FPGA_LED1") (class "Default")
      (node (ref "R9") (pin "1") (pinfunction "1_1") (pintype "bidirectional"))
      (node (ref "U4") (pin "143") (pinfunction "IO_L1N_VREF_0_143") (pintype "bidirectional"))
    )
    (net (code "48") (name "FPGA_LED2") (class "Default")
      (node (ref "R10") (pin "1") (pinfunction "1_1") (pintype "bidirectional"))
      (node (ref "U4") (pin "142") (pinfunction "IO_L2P_0_142") (pintype "bidirectional"))
    )
    (net (code "49") (name "FPGA_LED3") (class "Default")
      (node (ref "R11") (pin "1") (pinfunction "1_1") (pintype "bidirectional"))
      (node (ref "U4") (pin "141") (pinfunction "IO_L2N_0_141") (pintype "bidirectional"))
    )
    (net (code "50") (name "FPGA_RESET") (class "Default")
      (node (ref "R15") (pin "1") (pinfunction "1_1") (pintype "bidirectional"))
      (node (ref "S2") (pin "2") (pinfunction "3_2") (pintype "bidirectional"))
      (node (ref "U4") (pin "37") (pinfunction "PROGRAM_B_2_37") (pintype "bidirectional"))
    )
    (net (code "51") (name "FPGA_VCCAUX") (class "Default")
      (node (ref "C10") (pin "1") (pinfunction "P$1_1") (pintype "bidirectional"))
      (node (ref "C11") (pin "1") (pinfunction "P$1_1") (pintype "bidirectional"))
      (node (ref "C12") (pin "1") (pinfunction "P$1_1") (pintype "bidirectional"))
      (node (ref "C14") (pin "1") (pinfunction "P$1_1") (pintype "bidirectional"))
      (node (ref "C15") (pin "1") (pinfunction "P$1_1") (pintype "bidirectional"))
      (node (ref "C16") (pin "1") (pinfunction "P$1_1") (pintype "bidirectional"))
      (node (ref "C17") (pin "1") (pinfunction "P$1_1") (pintype "bidirectional"))
      (node (ref "C18") (pin "1") (pinfunction "P$1_1") (pintype "bidirectional"))
      (node (ref "C19") (pin "1") (pinfunction "P$1_1") (pintype "bidirectional"))
      (node (ref "C2") (pin "1") (pinfunction "P$1_1") (pintype "bidirectional"))
      (node (ref "C20") (pin "1") (pinfunction "P$1_1") (pintype "bidirectional"))
      (node (ref "C21") (pin "1") (pinfunction "P$1_1") (pintype "bidirectional"))
      (node (ref "C22") (pin "1") (pinfunction "P$1_1") (pintype "bidirectional"))
      (node (ref "C23") (pin "1") (pinfunction "P$1_1") (pintype "bidirectional"))
      (node (ref "C24") (pin "1") (pinfunction "P$1_1") (pintype "bidirectional"))
      (node (ref "C3") (pin "1") (pinfunction "P$1_1") (pintype "bidirectional"))
      (node (ref "C4") (pin "2") (pinfunction "P$2_2") (pintype "bidirectional"))
      (node (ref "C6") (pin "1") (pinfunction "P$1_1") (pintype "bidirectional"))
      (node (ref "C7") (pin "1") (pinfunction "P$1_1") (pintype "bidirectional"))
      (node (ref "C8") (pin "1") (pinfunction "P$1_1") (pintype "bidirectional"))
      (node (ref "J3") (pin "1") (pinfunction "1_1") (pintype "bidirectional"))
      (node (ref "R12") (pin "1") (pinfunction "1_1") (pintype "bidirectional"))
      (node (ref "R13") (pin "1") (pinfunction "1_1") (pintype "bidirectional"))
      (node (ref "R14") (pin "1") (pinfunction "1_1") (pintype "bidirectional"))
      (node (ref "R15") (pin "2") (pinfunction "2_2") (pintype "bidirectional"))
      (node (ref "R19") (pin "1") (pinfunction "1_1") (pintype "bidirectional"))
      (node (ref "U4") (pin "103") (pinfunction "VCCO_1_103") (pintype "bidirectional"))
      (node (ref "U4") (pin "122") (pinfunction "VCCO_0_122") (pintype "bidirectional"))
      (node (ref "U4") (pin "125") (pinfunction "VCCO_0_125") (pintype "bidirectional"))
      (node (ref "U4") (pin "129") (pinfunction "VCCAUX_129") (pintype "bidirectional"))
      (node (ref "U4") (pin "135") (pinfunction "VCCO_0_135") (pintype "bidirectional"))
      (node (ref "U4") (pin "18") (pinfunction "VCCO_3_18") (pintype "bidirectional"))
      (node (ref "U4") (pin "20") (pinfunction "VCCAUX_20") (pintype "bidirectional"))
      (node (ref "U4") (pin "31") (pinfunction "VCCO_3_31") (pintype "bidirectional"))
      (node (ref "U4") (pin "36") (pinfunction "VCCAUX_36") (pintype "bidirectional"))
      (node (ref "U4") (pin "4") (pinfunction "VCCO_3_4") (pintype "bidirectional"))
      (node (ref "U4") (pin "42") (pinfunction "VCCO_2_42") (pintype "bidirectional"))
      (node (ref "U4") (pin "53") (pinfunction "VCCAUX_53") (pintype "bidirectional"))
      (node (ref "U4") (pin "63") (pinfunction "VCCO_2_63") (pintype "bidirectional"))
      (node (ref "U4") (pin "76") (pinfunction "VCCO_1_76") (pintype "bidirectional"))
      (node (ref "U4") (pin "86") (pinfunction "VCCO_1_86") (pintype "bidirectional"))
      (node (ref "U4") (pin "90") (pinfunction "VCCAUX_90") (pintype "bidirectional"))
      (node (ref "U5") (pin "8") (pinfunction "VDD_8") (pintype "bidirectional"))
      (node (ref "U7") (pin "2") (pinfunction "SENSE1-_2") (pintype "bidirectional"))
      (node (ref "X2") (pin "1") (pinfunction "EN_1") (pintype "bidirectional"))
      (node (ref "X2") (pin "4") (pinfunction "VS+_4") (pintype "bidirectional"))
      (node (ref "X3") (pin "1") (pinfunction "EN_1") (pintype "bidirectional"))
      (node (ref "X3") (pin "4") (pinfunction "VS+_4") (pintype "bidirectional"))
    )
    (net (code "52") (name "FPGA_VCCINT") (class "Default")
      (node (ref "C1") (pin "1") (pinfunction "P$1_1") (pintype "bidirectional"))
      (node (ref "C13") (pin "1") (pinfunction "P$1_1") (pintype "bidirectional"))
      (node (ref "C5") (pin "1") (pinfunction "P$1_1") (pintype "bidirectional"))
      (node (ref "C9") (pin "1") (pinfunction "P$1_1") (pintype "bidirectional"))
      (node (ref "J4") (pin "1") (pinfunction "1_1") (pintype "bidirectional"))
      (node (ref "R17") (pin "1") (pinfunction "1_1") (pintype "bidirectional"))
      (node (ref "U4") (pin "128") (pinfunction "VCCINT_128") (pintype "bidirectional"))
      (node (ref "U4") (pin "19") (pinfunction "VCCINT_19") (pintype "bidirectional"))
      (node (ref "U4") (pin "28") (pinfunction "VCCINT_28") (pintype "bidirectional"))
      (node (ref "U4") (pin "52") (pinfunction "VCCINT_52") (pintype "bidirectional"))
      (node (ref "U4") (pin "89") (pinfunction "VCCINT_89") (pintype "bidirectional"))
      (node (ref "U7") (pin "4") (pinfunction "SENSE2-_4") (pintype "bidirectional"))
    )
    (net (code "53") (name "GND") (class "Default")
      (node (ref "C1") (pin "2") (pinfunction "P$2_2") (pintype "bidirectional"))
      (node (ref "C10") (pin "2") (pinfunction "P$2_2") (pintype "bidirectional"))
      (node (ref "C11") (pin "2") (pinfunction "P$2_2") (pintype "bidirectional"))
      (node (ref "C12") (pin "2") (pinfunction "P$2_2") (pintype "bidirectional"))
      (node (ref "C13") (pin "2") (pinfunction "P$2_2") (pintype "bidirectional"))
      (node (ref "C14") (pin "2") (pinfunction "P$2_2") (pintype "bidirectional"))
      (node (ref "C15") (pin "2") (pinfunction "P$2_2") (pintype "bidirectional"))
      (node (ref "C16") (pin "2") (pinfunction "P$2_2") (pintype "bidirectional"))
      (node (ref "C17") (pin "2") (pinfunction "P$2_2") (pintype "bidirectional"))
      (node (ref "C18") (pin "2") (pinfunction "P$2_2") (pintype "bidirectional"))
      (node (ref "C19") (pin "2") (pinfunction "P$2_2") (pintype "bidirectional"))
      (node (ref "C2") (pin "2") (pinfunction "P$2_2") (pintype "bidirectional"))
      (node (ref "C20") (pin "2") (pinfunction "P$2_2") (pintype "bidirectional"))
      (node (ref "C21") (pin "2") (pinfunction "P$2_2") (pintype "bidirectional"))
      (node (ref "C22") (pin "2") (pinfunction "P$2_2") (pintype "bidirectional"))
      (node (ref "C23") (pin "2") (pinfunction "P$2_2") (pintype "bidirectional"))
      (node (ref "C24") (pin "2") (pinfunction "P$2_2") (pintype "bidirectional"))
      (node (ref "C25") (pin "2") (pinfunction "P$2_2") (pintype "bidirectional"))
      (node (ref "C26") (pin "1") (pinfunction "P$1_1") (pintype "bidirectional"))
      (node (ref "C27") (pin "1") (pinfunction "P$1_1") (pintype "bidirectional"))
      (node (ref "C28") (pin "2") (pinfunction "P$2_2") (pintype "bidirectional"))
      (node (ref "C29") (pin "2") (pinfunction "P$2_2") (pintype "bidirectional"))
      (node (ref "C3") (pin "2") (pinfunction "P$2_2") (pintype "bidirectional"))
      (node (ref "C30") (pin "2") (pinfunction "P$2_2") (pintype "bidirectional"))
      (node (ref "C31") (pin "2") (pinfunction "P$2_2") (pintype "bidirectional"))
      (node (ref "C4") (pin "1") (pinfunction "P$1_1") (pintype "bidirectional"))
      (node (ref "C5") (pin "2") (pinfunction "P$2_2") (pintype "bidirectional"))
      (node (ref "C6") (pin "2") (pinfunction "P$2_2") (pintype "bidirectional"))
      (node (ref "C7") (pin "2") (pinfunction "P$2_2") (pintype "bidirectional"))
      (node (ref "C8") (pin "2") (pinfunction "P$2_2") (pintype "bidirectional"))
      (node (ref "C9") (pin "2") (pinfunction "P$2_2") (pintype "bidirectional"))
      (node (ref "J1") (pin "6") (pinfunction "GND_6") (pintype "bidirectional"))
      (node (ref "J3") (pin "3") (pinfunction "2_3") (pintype "bidirectional"))
      (node (ref "J4") (pin "3") (pinfunction "2_3") (pintype "bidirectional"))
      (node (ref "J7") (pin "P$2") (pinfunction "GND_P$2") (pintype "bidirectional"))
      (node (ref "J8") (pin "5") (pinfunction "GND_5") (pintype "bidirectional"))
      (node (ref "LED0") (pin "2") (pinfunction "2_2") (pintype "bidirectional"))
      (node (ref "LED1") (pin "2") (pinfunction "2_2") (pintype "bidirectional"))
      (node (ref "LED2") (pin "2") (pinfunction "2_2") (pintype "bidirectional"))
      (node (ref "LED3") (pin "2") (pinfunction "2_2") (pintype "bidirectional"))
      (node (ref "LED4") (pin "2") (pinfunction "2_2") (pintype "bidirectional"))
      (node (ref "LED5") (pin "2") (pinfunction "2_2") (pintype "bidirectional"))
      (node (ref "LED6") (pin "2") (pinfunction "2_2") (pintype "bidirectional"))
      (node (ref "LED7") (pin "2") (pinfunction "2_2") (pintype "bidirectional"))
      (node (ref "R20") (pin "1") (pinfunction "1_1") (pintype "bidirectional"))
      (node (ref "R21") (pin "1") (pinfunction "1_1") (pintype "bidirectional"))
      (node (ref "R23") (pin "1") (pinfunction "1_1") (pintype "bidirectional"))
      (node (ref "R24") (pin "2") (pinfunction "2_2") (pintype "bidirectional"))
      (node (ref "R29") (pin "2") (pinfunction "2_2") (pintype "bidirectional"))
      (node (ref "R30") (pin "1") (pinfunction "1_1") (pintype "bidirectional"))
      (node (ref "R32") (pin "1") (pinfunction "1_1") (pintype "bidirectional"))
      (node (ref "S1") (pin "1") (pinfunction "1_1") (pintype "bidirectional"))
      (node (ref "S2") (pin "1") (pinfunction "1_1") (pintype "bidirectional"))
      (node (ref "S3") (pin "3") (pinfunction "2Y_3") (pintype "bidirectional"))
      (node (ref "S3") (pin "4") (pinfunction "1Y_4") (pintype "bidirectional"))
      (node (ref "U1") (pin "22") (pinfunction "GND_22") (pintype "bidirectional"))
      (node (ref "U1") (pin "53") (pinfunction "GND_53") (pintype "bidirectional"))
      (node (ref "U1") (pin "63") (pinfunction "GND_63") (pintype "bidirectional"))
      (node (ref "U1") (pin "PAD") (pinfunction "GND_PAD") (pintype "bidirectional"))
      (node (ref "U1") (pin "VIA1") (pinfunction "GND_VIA1") (pintype "bidirectional"))
      (node (ref "U1") (pin "VIA2") (pinfunction "GND_VIA2") (pintype "bidirectional"))
      (node (ref "U1") (pin "VIA3") (pinfunction "GND_VIA3") (pintype "bidirectional"))
      (node (ref "U1") (pin "VIA4") (pinfunction "GND_VIA4") (pintype "bidirectional"))
      (node (ref "U1") (pin "VIA5") (pinfunction "GND_VIA5") (pintype "bidirectional"))
      (node (ref "U1") (pin "VIA6") (pinfunction "GND_VIA6") (pintype "bidirectional"))
      (node (ref "U1") (pin "VIA7") (pinfunction "GND_VIA7") (pintype "bidirectional"))
      (node (ref "U1") (pin "VIA8") (pinfunction "GND_VIA8") (pintype "bidirectional"))
      (node (ref "U1") (pin "VIA9") (pinfunction "GND_VIA9") (pintype "bidirectional"))
      (node (ref "U10") (pin "9") (pinfunction "GND_9") (pintype "bidirectional"))
      (node (ref "U2") (pin "4") (pinfunction "VSS_4") (pintype "bidirectional"))
      (node (ref "U3") (pin "1") (pinfunction "GND_1") (pintype "bidirectional"))
      (node (ref "U3") (pin "11") (pinfunction "GND_11") (pintype "bidirectional"))
      (node (ref "U3") (pin "12") (pinfunction "GND_12") (pintype "bidirectional"))
      (node (ref "U4") (pin "108") (pinfunction "GND_108") (pintype "bidirectional"))
      (node (ref "U4") (pin "113") (pinfunction "GND_113") (pintype "bidirectional"))
      (node (ref "U4") (pin "13") (pinfunction "GND_13") (pintype "bidirectional"))
      (node (ref "U4") (pin "130") (pinfunction "GND_130") (pintype "bidirectional"))
      (node (ref "U4") (pin "136") (pinfunction "GND_136") (pintype "bidirectional"))
      (node (ref "U4") (pin "25") (pinfunction "GND_25") (pintype "bidirectional"))
      (node (ref "U4") (pin "3") (pinfunction "GND_3") (pintype "bidirectional"))
      (node (ref "U4") (pin "47") (pinfunction "IO_L48N_RDWR_B_VREF_2_47") (pintype "bidirectional"))
      (node (ref "U4") (pin "49") (pinfunction "GND_49") (pintype "bidirectional"))
      (node (ref "U4") (pin "54") (pinfunction "GND_54") (pintype "bidirectional"))
      (node (ref "U4") (pin "68") (pinfunction "GND_68") (pintype "bidirectional"))
      (node (ref "U4") (pin "77") (pinfunction "GND_77") (pintype "bidirectional"))
      (node (ref "U4") (pin "91") (pinfunction "GND_91") (pintype "bidirectional"))
      (node (ref "U4") (pin "96") (pinfunction "GND_96") (pintype "bidirectional"))
      (node (ref "U5") (pin "4") (pinfunction "VSS_4") (pintype "bidirectional"))
      (node (ref "U6") (pin "5") (pinfunction "GND_5") (pintype "bidirectional"))
      (node (ref "U6") (pin "P$1") (pinfunction "GND_P$1") (pintype "bidirectional"))
      (node (ref "U6") (pin "P$2") (pinfunction "GND_P$2") (pintype "bidirectional"))
      (node (ref "U6") (pin "P$3") (pinfunction "GND_P$3") (pintype "bidirectional"))
      (node (ref "U6") (pin "P$4") (pinfunction "GND_P$4") (pintype "bidirectional"))
      (node (ref "U7") (pin "5") (pinfunction "GND_5") (pintype "bidirectional"))
      (node (ref "U7") (pin "P$1") (pinfunction "GND_P$1") (pintype "bidirectional"))
      (node (ref "U7") (pin "P$2") (pinfunction "GND_P$2") (pintype "bidirectional"))
      (node (ref "U7") (pin "P$3") (pinfunction "GND_P$3") (pintype "bidirectional"))
      (node (ref "U7") (pin "P$4") (pinfunction "GND_P$4") (pintype "bidirectional"))
      (node (ref "U8") (pin "5") (pinfunction "GND_5") (pintype "bidirectional"))
      (node (ref "U8") (pin "P$1") (pinfunction "GND_P$1") (pintype "bidirectional"))
      (node (ref "U8") (pin "P$2") (pinfunction "GND_P$2") (pintype "bidirectional"))
      (node (ref "U8") (pin "P$3") (pinfunction "GND_P$3") (pintype "bidirectional"))
      (node (ref "U8") (pin "P$4") (pinfunction "GND_P$4") (pintype "bidirectional"))
      (node (ref "U9") (pin "17") (pinfunction "GND_17") (pintype "bidirectional"))
      (node (ref "U9") (pin "20") (pinfunction "GND_20") (pintype "bidirectional"))
      (node (ref "U9") (pin "24") (pinfunction "AGND_24") (pintype "bidirectional"))
      (node (ref "U9") (pin "26") (pinfunction "TEST_26") (pintype "bidirectional"))
      (node (ref "U9") (pin "33") (pinfunction "GND_33") (pintype "bidirectional"))
      (node (ref "U9") (pin "4") (pinfunction "GND_4") (pintype "bidirectional"))
      (node (ref "U9") (pin "P$1") (pinfunction "GND_P$1") (pintype "bidirectional"))
      (node (ref "U9") (pin "P$2") (pinfunction "GND_P$2") (pintype "bidirectional"))
      (node (ref "U9") (pin "P$3") (pinfunction "GND_P$3") (pintype "bidirectional"))
      (node (ref "U9") (pin "P$4") (pinfunction "GND_P$4") (pintype "bidirectional"))
      (node (ref "U9") (pin "P$5") (pinfunction "GND_P$5") (pintype "bidirectional"))
      (node (ref "U9") (pin "P$6") (pinfunction "GND_P$6") (pintype "bidirectional"))
      (node (ref "U9") (pin "P$7") (pinfunction "GND_P$7") (pintype "bidirectional"))
      (node (ref "U9") (pin "P$8") (pinfunction "GND_P$8") (pintype "bidirectional"))
      (node (ref "U9") (pin "P$9") (pinfunction "GND_P$9") (pintype "bidirectional"))
      (node (ref "X2") (pin "2") (pinfunction "GND_2") (pintype "bidirectional"))
      (node (ref "X3") (pin "2") (pinfunction "GND_2") (pintype "bidirectional"))
    )
    (net (code "54") (name "INIT_B") (class "Default")
      (node (ref "U1") (pin "17") (pinfunction "PB7_OC2/OC1C_17") (pintype "bidirectional"))
      (node (ref "U4") (pin "39") (pinfunction "IO_L65P_INIT_B_2_39") (pintype "bidirectional"))
    )
    (net (code "55") (name "JTAG_TCK") (class "Default")
      (node (ref "J7") (pin "P$3") (pinfunction "TCK_P$3") (pintype "bidirectional"))
      (node (ref "U1") (pin "57") (pinfunction "PF4_ADC4/TCK_57") (pintype "bidirectional"))
      (node (ref "U4") (pin "109") (pinfunction "TCK_109") (pintype "bidirectional"))
    )
    (net (code "56") (name "JTAG_TDI") (class "Default")
      (node (ref "J7") (pin "P$5") (pinfunction "TDI_P$5") (pintype "bidirectional"))
      (node (ref "U1") (pin "55") (pinfunction "PF6_ADC6/TDO_55") (pintype "bidirectional"))
      (node (ref "U4") (pin "110") (pinfunction "TDI_110") (pintype "bidirectional"))
    )
    (net (code "57") (name "JTAG_TDO") (class "Default")
      (node (ref "J7") (pin "P$4") (pinfunction "TDO_P$4") (pintype "bidirectional"))
      (node (ref "U1") (pin "56") (pinfunction "PF5_ADC5/TMS_56") (pintype "bidirectional"))
      (node (ref "U4") (pin "106") (pinfunction "TDO_106") (pintype "bidirectional"))
    )
    (net (code "58") (name "JTAG_TMS") (class "Default")
      (node (ref "J7") (pin "P$6") (pinfunction "TMS_P$6") (pintype "bidirectional"))
      (node (ref "U1") (pin "54") (pinfunction "PF7_ADC7/TDI_54") (pintype "bidirectional"))
      (node (ref "U4") (pin "107") (pinfunction "TMS_107") (pintype "bidirectional"))
    )
    (net (code "59") (name "MCU_CS") (class "Default")
      (node (ref "U1") (pin "10") (pinfunction "PB0_SS#_10") (pintype "bidirectional"))
    )
    (net (code "60") (name "MCU_FLASH_CE") (class "Default")
      (node (ref "R2") (pin "2") (pinfunction "2_2") (pintype "bidirectional"))
      (node (ref "U1") (pin "14") (pinfunction "PB4_OC0_14") (pintype "bidirectional"))
      (node (ref "U2") (pin "1") (pinfunction "CE_1") (pintype "bidirectional"))
    )
    (net (code "61") (name "MCU_GPIO_0") (class "Default")
      (node (ref "J2") (pin "4") (pinfunction "4_4") (pintype "bidirectional"))
      (node (ref "U1") (pin "58") (pinfunction "PF3_ADC3_58") (pintype "bidirectional"))
    )
    (net (code "62") (name "MCU_GPIO_1") (class "Default")
      (node (ref "J2") (pin "3") (pinfunction "3_3") (pintype "bidirectional"))
      (node (ref "U1") (pin "59") (pinfunction "PF2_ADC2_59") (pintype "bidirectional"))
    )
    (net (code "63") (name "MCU_GPIO_2") (class "Default")
      (node (ref "J2") (pin "2") (pinfunction "2_2") (pintype "bidirectional"))
      (node (ref "U1") (pin "60") (pinfunction "PF1_ADC1_60") (pintype "bidirectional"))
    )
    (net (code "64") (name "MCU_GPIO_3") (class "Default")
      (node (ref "J2") (pin "1") (pinfunction "1_1") (pintype "bidirectional"))
      (node (ref "U1") (pin "61") (pinfunction "PF0_ADC0_61") (pintype "bidirectional"))
    )
    (net (code "65") (name "MCU_LED0") (class "Default")
      (node (ref "R3") (pin "1") (pinfunction "1_1") (pintype "bidirectional"))
      (node (ref "U1") (pin "16") (pinfunction "PB6_OC1B_16") (pintype "bidirectional"))
    )
    (net (code "66") (name "MCU_LED1") (class "Default")
      (node (ref "R4") (pin "1") (pinfunction "1_1") (pintype "bidirectional"))
      (node (ref "U1") (pin "15") (pinfunction "PB5_OC1A_15") (pintype "bidirectional"))
    )
    (net (code "67") (name "MCU_LED2") (class "Default")
      (node (ref "R5") (pin "1") (pinfunction "1_1") (pintype "bidirectional"))
      (node (ref "U1") (pin "4") (pinfunction "PE2_XCK0/AIN0_4") (pintype "bidirectional"))
    )
    (net (code "68") (name "MCU_LED3") (class "Default")
      (node (ref "R6") (pin "1") (pinfunction "1_1") (pintype "bidirectional"))
      (node (ref "U1") (pin "5") (pinfunction "PE3_OC3A/AIN1_5") (pintype "bidirectional"))
    )
    (net (code "69") (name "MCU_MISO") (class "Default")
      (node (ref "U1") (pin "13") (pinfunction "PB3_MISO_13") (pintype "bidirectional"))
      (node (ref "U2") (pin "2") (pinfunction "SO_2") (pintype "bidirectional"))
      (node (ref "U3") (pin "7") (pinfunction "SDO_7") (pintype "bidirectional"))
    )
    (net (code "70") (name "MCU_MOSI") (class "Default")
      (node (ref "U1") (pin "12") (pinfunction "PB2_MOSI_12") (pintype "bidirectional"))
      (node (ref "U2") (pin "5") (pinfunction "SI_5") (pintype "bidirectional"))
      (node (ref "U3") (pin "5") (pinfunction "SDI_5") (pintype "bidirectional"))
    )
    (net (code "71") (name "MCU_RESET") (class "Default")
      (node (ref "J1") (pin "5") (pinfunction "RST_5") (pintype "bidirectional"))
      (node (ref "R7") (pin "1") (pinfunction "1_1") (pintype "bidirectional"))
      (node (ref "S1") (pin "2") (pinfunction "3_2") (pintype "bidirectional"))
      (node (ref "U1") (pin "20") (pinfunction "_RESET_20") (pintype "bidirectional"))
    )
    (net (code "72") (name "MCU_RX0{slash}PDI") (class "Default")
      (node (ref "J1") (pin "4") (pinfunction "MOSI_4") (pintype "bidirectional"))
      (node (ref "U1") (pin "2") (pinfunction "PE0_RXD0/PDI_2") (pintype "bidirectional"))
      (node (ref "U9") (pin "30") (pinfunction "TXD_30") (pintype "bidirectional"))
    )
    (net (code "73") (name "MCU_SCK") (class "Default")
      (node (ref "J1") (pin "3") (pinfunction "SCK_3") (pintype "bidirectional"))
      (node (ref "U1") (pin "11") (pinfunction "PB1_SCK_11") (pintype "bidirectional"))
      (node (ref "U2") (pin "6") (pinfunction "SCK_6") (pintype "bidirectional"))
      (node (ref "U3") (pin "6") (pinfunction "SCK_6") (pintype "bidirectional"))
    )
    (net (code "74") (name "MCU_TX0{slash}PDO") (class "Default")
      (node (ref "J1") (pin "1") (pinfunction "MISO_1") (pintype "bidirectional"))
      (node (ref "U1") (pin "3") (pinfunction "PE1_TXD0/PDO_3") (pintype "bidirectional"))
      (node (ref "U9") (pin "2") (pinfunction "RXD_2") (pintype "bidirectional"))
    )
    (net (code "75") (name "MCU_VCC") (class "Default")
      (node (ref "R1") (pin "1") (pinfunction "1_1") (pintype "bidirectional"))
      (node (ref "R2") (pin "1") (pinfunction "1_1") (pintype "bidirectional"))
      (node (ref "R22") (pin "1") (pinfunction "1_1") (pintype "bidirectional"))
      (node (ref "R7") (pin "2") (pinfunction "2_2") (pintype "bidirectional"))
      (node (ref "U1") (pin "21") (pinfunction "VCC_21") (pintype "bidirectional"))
      (node (ref "U1") (pin "52") (pinfunction "VCC_52") (pintype "bidirectional"))
      (node (ref "U1") (pin "62") (pinfunction "AVREF_62") (pintype "bidirectional"))
      (node (ref "U1") (pin "64") (pinfunction "AVCC_64") (pintype "bidirectional"))
      (node (ref "U2") (pin "3") (pinfunction "WP_3") (pintype "bidirectional"))
      (node (ref "U2") (pin "7") (pinfunction "HOLD_7") (pintype "bidirectional"))
      (node (ref "U2") (pin "8") (pinfunction "VDD_8") (pintype "bidirectional"))
      (node (ref "U8") (pin "4") (pinfunction "SENSE2-_4") (pintype "bidirectional"))
    )
    (net (code "76") (name "MODE0") (class "Default")
      (node (ref "R12") (pin "2") (pinfunction "2_2") (pintype "bidirectional"))
      (node (ref "S3") (pin "1") (pinfunction "1X_1") (pintype "bidirectional"))
      (node (ref "U4") (pin "69") (pinfunction "IO_L1N_M0_CMPMISO_2_69") (pintype "bidirectional"))
    )
    (net (code "77") (name "MODE1") (class "Default")
      (node (ref "R13") (pin "2") (pinfunction "2_2") (pintype "bidirectional"))
      (node (ref "S3") (pin "2") (pinfunction "2X_2") (pintype "bidirectional"))
      (node (ref "U4") (pin "60") (pinfunction "IO_L13P_M1_2_60") (pintype "bidirectional"))
    )
    (net (code "78") (name "N$4") (class "Default")
      (node (ref "U9") (pin "28") (pinfunction "OSCO_28") (pintype "bidirectional"))
    )
    (net (code "79") (name "N$5") (class "Default")
      (node (ref "U9") (pin "27") (pinfunction "OSCI_27") (pintype "bidirectional"))
    )
    (net (code "80") (name "N$6") (class "Default")
      (node (ref "U9") (pin "18") (pinfunction "RESET#_18") (pintype "bidirectional"))
    )
    (net (code "81") (name "N$12") (class "Default")
      (node (ref "U4") (pin "50") (pinfunction "IO_L31N_GCLK30_D15_2_50") (pintype "bidirectional"))
    )
    (net (code "82") (name "N$17") (class "Default")
      (node (ref "U9") (pin "32") (pinfunction "RTS#_32") (pintype "bidirectional"))
    )
    (net (code "83") (name "N$18") (class "Default")
      (node (ref "U9") (pin "8") (pinfunction "CTS#_8") (pintype "bidirectional"))
    )
    (net (code "84") (name "N$19") (class "Default")
      (node (ref "U9") (pin "31") (pinfunction "DTR#_31") (pintype "bidirectional"))
    )
    (net (code "85") (name "N$20") (class "Default")
      (node (ref "U9") (pin "6") (pinfunction "DSR#_6") (pintype "bidirectional"))
    )
    (net (code "86") (name "N$21") (class "Default")
      (node (ref "U9") (pin "7") (pinfunction "DCD#_7") (pintype "bidirectional"))
    )
    (net (code "87") (name "N$22") (class "Default")
      (node (ref "U9") (pin "3") (pinfunction "RI#_3") (pintype "bidirectional"))
    )
    (net (code "88") (name "N$26") (class "Default")
      (node (ref "U9") (pin "9") (pinfunction "CBUS4_9") (pintype "bidirectional"))
    )
    (net (code "89") (name "N$31") (class "Default")
      (node (ref "U4") (pin "140") (pinfunction "IO_L3P_0_140") (pintype "bidirectional"))
    )
    (net (code "90") (name "N$34") (class "Default")
      (node (ref "U4") (pin "87") (pinfunction "IO_L42N_GCLK6_TRDY1_1_87") (pintype "bidirectional"))
    )
    (net (code "91") (name "N$35") (class "Default")
      (node (ref "U4") (pin "88") (pinfunction "IO_L42P_GCLK7_1_88") (pintype "bidirectional"))
    )
    (net (code "92") (name "N$36") (class "Default")
      (node (ref "U4") (pin "92") (pinfunction "IO_L41N_GCLK8_1_92") (pintype "bidirectional"))
    )
    (net (code "93") (name "N$37") (class "Default")
      (node (ref "U4") (pin "93") (pinfunction "IO_L41P_GCLK9_IRDY1_1_93") (pintype "bidirectional"))
    )
    (net (code "94") (name "N$91") (class "Default")
      (node (ref "U4") (pin "57") (pinfunction "IO_L14N_D12_2_57") (pintype "bidirectional"))
    )
    (net (code "95") (name "N$93") (class "Default")
      (node (ref "U4") (pin "58") (pinfunction "IO_L14P_D11_2_58") (pintype "bidirectional"))
    )
    (net (code "96") (name "N$94") (class "Default")
      (node (ref "U4") (pin "59") (pinfunction "IO_L13N_D10_2_59") (pintype "bidirectional"))
    )
    (net (code "97") (name "N$96") (class "Default")
      (node (ref "U4") (pin "56") (pinfunction "IO_L30P_GCLK1_D13_2_56") (pintype "bidirectional"))
    )
    (net (code "98") (name "N$98") (class "Default")
      (node (ref "U4") (pin "41") (pinfunction "IO_L64P_D8_2_41") (pintype "bidirectional"))
    )
    (net (code "99") (name "N$941") (class "Default")
      (node (ref "U4") (pin "40") (pinfunction "IO_L64N_D9_2_40") (pintype "bidirectional"))
    )
    (net (code "100") (name "Net-(C28-P$1)") (class "Default")
      (node (ref "C28") (pin "1") (pinfunction "P$1_1") (pintype "bidirectional"))
      (node (ref "U9") (pin "16") (pinfunction "3V3OUT_16") (pintype "bidirectional"))
    )
    (net (code "101") (name "Net-(J8-D+)") (class "Default")
      (node (ref "J8") (pin "3") (pinfunction "D+_3") (pintype "bidirectional"))
      (node (ref "U9") (pin "14") (pinfunction "USBDP_14") (pintype "bidirectional"))
    )
    (net (code "102") (name "Net-(J8-D-)") (class "Default")
      (node (ref "J8") (pin "2") (pinfunction "D-_2") (pintype "bidirectional"))
      (node (ref "U9") (pin "15") (pinfunction "USBDM_15") (pintype "bidirectional"))
    )
    (net (code "103") (name "Net-(L2-P$2)") (class "Default")
      (node (ref "L2") (pin "2") (pinfunction "P$2_2") (pintype "bidirectional"))
      (node (ref "U10") (pin "4") (pinfunction "SW1_4") (pintype "bidirectional"))
    )
    (net (code "104") (name "Net-(L3-P$1)") (class "Default")
      (node (ref "L3") (pin "1") (pinfunction "P$1_1") (pintype "bidirectional"))
      (node (ref "U10") (pin "6") (pinfunction "SW2_6") (pintype "bidirectional"))
    )
    (net (code "105") (name "Net-(LED0-Pad1)") (class "Default")
      (node (ref "LED0") (pin "1") (pinfunction "1_1") (pintype "bidirectional"))
      (node (ref "R3") (pin "2") (pinfunction "2_2") (pintype "bidirectional"))
    )
    (net (code "106") (name "Net-(LED1-Pad1)") (class "Default")
      (node (ref "LED1") (pin "1") (pinfunction "1_1") (pintype "bidirectional"))
      (node (ref "R4") (pin "2") (pinfunction "2_2") (pintype "bidirectional"))
    )
    (net (code "107") (name "Net-(LED2-Pad1)") (class "Default")
      (node (ref "LED2") (pin "1") (pinfunction "1_1") (pintype "bidirectional"))
      (node (ref "R5") (pin "2") (pinfunction "2_2") (pintype "bidirectional"))
    )
    (net (code "108") (name "Net-(LED3-Pad1)") (class "Default")
      (node (ref "LED3") (pin "1") (pinfunction "1_1") (pintype "bidirectional"))
      (node (ref "R6") (pin "2") (pinfunction "2_2") (pintype "bidirectional"))
    )
    (net (code "109") (name "Net-(LED4-Pad1)") (class "Default")
      (node (ref "LED4") (pin "1") (pinfunction "1_1") (pintype "bidirectional"))
      (node (ref "R8") (pin "2") (pinfunction "2_2") (pintype "bidirectional"))
    )
    (net (code "110") (name "Net-(LED5-Pad1)") (class "Default")
      (node (ref "LED5") (pin "1") (pinfunction "1_1") (pintype "bidirectional"))
      (node (ref "R9") (pin "2") (pinfunction "2_2") (pintype "bidirectional"))
    )
    (net (code "111") (name "Net-(LED6-Pad1)") (class "Default")
      (node (ref "LED6") (pin "1") (pinfunction "1_1") (pintype "bidirectional"))
      (node (ref "R10") (pin "2") (pinfunction "2_2") (pintype "bidirectional"))
    )
    (net (code "112") (name "Net-(LED7-Pad1)") (class "Default")
      (node (ref "LED7") (pin "1") (pinfunction "1_1") (pintype "bidirectional"))
      (node (ref "R11") (pin "2") (pinfunction "2_2") (pintype "bidirectional"))
    )
    (net (code "113") (name "Net-(PWR-Pad2)") (class "Default")
      (node (ref "PWR") (pin "2") (pinfunction "2_2") (pintype "bidirectional"))
      (node (ref "R32") (pin "2") (pinfunction "2_2") (pintype "bidirectional"))
    )
    (net (code "114") (name "Net-(R26-Pad2)") (class "Default")
      (node (ref "R26") (pin "2") (pinfunction "2_2") (pintype "bidirectional"))
      (node (ref "TX") (pin "2") (pinfunction "2_2") (pintype "bidirectional"))
    )
    (net (code "115") (name "Net-(R27-Pad2)") (class "Default")
      (node (ref "R27") (pin "2") (pinfunction "2_2") (pintype "bidirectional"))
      (node (ref "RX") (pin "2") (pinfunction "2_2") (pintype "bidirectional"))
    )
    (net (code "116") (name "Net-(U1-XTAL1)") (class "Default")
      (node (ref "U1") (pin "24") (pinfunction "XTAL1_24") (pintype "bidirectional"))
      (node (ref "X1") (pin "4") (pinfunction "P$2_4") (pintype "bidirectional"))
    )
    (net (code "117") (name "Net-(U1-XTAL2)") (class "Default")
      (node (ref "U1") (pin "23") (pinfunction "XTAL2_23") (pintype "bidirectional"))
      (node (ref "X1") (pin "2") (pinfunction "P$1_2") (pintype "bidirectional"))
    )
    (net (code "118") (name "Net-(U6-ADDR_SEL)") (class "Default")
      (node (ref "R20") (pin "2") (pinfunction "2_2") (pintype "bidirectional"))
      (node (ref "U6") (pin "6") (pinfunction "ADDR_SEL_6") (pintype "bidirectional"))
    )
    (net (code "119") (name "Net-(U7-ADDR_SEL)") (class "Default")
      (node (ref "R21") (pin "2") (pinfunction "2_2") (pintype "bidirectional"))
      (node (ref "U7") (pin "6") (pinfunction "ADDR_SEL_6") (pintype "bidirectional"))
    )
    (net (code "120") (name "Net-(U8-ADDR_SEL)") (class "Default")
      (node (ref "R23") (pin "2") (pinfunction "2_2") (pintype "bidirectional"))
      (node (ref "U8") (pin "6") (pinfunction "ADDR_SEL_6") (pintype "bidirectional"))
    )
    (net (code "121") (name "Net-(U9-CBUS2)") (class "Default")
      (node (ref "R26") (pin "1") (pinfunction "1_1") (pintype "bidirectional"))
      (node (ref "U9") (pin "10") (pinfunction "CBUS2_10") (pintype "bidirectional"))
    )
    (net (code "122") (name "Net-(U9-CBUS3)") (class "Default")
      (node (ref "R27") (pin "1") (pinfunction "1_1") (pintype "bidirectional"))
      (node (ref "U9") (pin "11") (pinfunction "CBUS3_11") (pintype "bidirectional"))
    )
    (net (code "123") (name "Net-(U10-VFB1)") (class "Default")
      (node (ref "R28") (pin "2") (pinfunction "2_2") (pintype "bidirectional"))
      (node (ref "R29") (pin "1") (pinfunction "1_1") (pintype "bidirectional"))
      (node (ref "U10") (pin "1") (pinfunction "VFB1_1") (pintype "bidirectional"))
    )
    (net (code "124") (name "Net-(U10-VFB2)") (class "Default")
      (node (ref "R30") (pin "2") (pinfunction "2_2") (pintype "bidirectional"))
      (node (ref "R31") (pin "1") (pinfunction "1_1") (pintype "bidirectional"))
      (node (ref "U10") (pin "8") (pinfunction "VFB2_8") (pintype "bidirectional"))
    )
    (net (code "125") (name "OSC_32") (class "Default")
      (node (ref "U4") (pin "94") (pinfunction "IO_L40N_GCLK10_1_94") (pintype "bidirectional"))
      (node (ref "X3") (pin "3") (pinfunction "OUTPUT_3") (pintype "bidirectional"))
    )
    (net (code "126") (name "OSC_50") (class "Default")
      (node (ref "U4") (pin "51") (pinfunction "IO_L31P_GCLK31_D14_2_51") (pintype "bidirectional"))
      (node (ref "X2") (pin "3") (pinfunction "OUTPUT_3") (pintype "bidirectional"))
    )
    (net (code "127") (name "RD") (class "Default")
      (node (ref "U1") (pin "34") (pinfunction "PG1_RD#_34") (pintype "bidirectional"))
      (node (ref "U4") (pin "75") (pinfunction "IO_L74P_AWAKE_1_75") (pintype "bidirectional"))
    )
    (net (code "128") (name "SELECTMAP_D0{slash}FPGA_MISO1") (class "Default")
      (node (ref "U1") (pin "32") (pinfunction "PD7_T2_32") (pintype "bidirectional"))
      (node (ref "U4") (pin "65") (pinfunction "IO_L3P_D0_DIN_MISO_MISO1_2_65") (pintype "bidirectional"))
      (node (ref "U5") (pin "2") (pinfunction "SO_2") (pintype "bidirectional"))
    )
    (net (code "129") (name "SELECTMAP_D1{slash}FPGA_MISO2") (class "Default")
      (node (ref "U1") (pin "31") (pinfunction "PD6_T1_31") (pintype "bidirectional"))
      (node (ref "U4") (pin "62") (pinfunction "IO_L12P_D1_MISO2_2_62") (pintype "bidirectional"))
      (node (ref "U5") (pin "3") (pinfunction "WP_3") (pintype "bidirectional"))
    )
    (net (code "130") (name "SELECTMAP_D2{slash}FPGA_MISO3") (class "Default")
      (node (ref "U1") (pin "30") (pinfunction "PD5_XCK1_30") (pintype "bidirectional"))
      (node (ref "U4") (pin "61") (pinfunction "IO_L12N_D2_MISO3_2_61") (pintype "bidirectional"))
      (node (ref "U5") (pin "7") (pinfunction "HOLD_7") (pintype "bidirectional"))
    )
    (net (code "131") (name "SELECTMAP_D3") (class "Default")
      (node (ref "U1") (pin "29") (pinfunction "PD4_ICP1_29") (pintype "bidirectional"))
      (node (ref "U4") (pin "46") (pinfunction "IO_L49P_D3_2_46") (pintype "bidirectional"))
    )
    (net (code "132") (name "SELECTMAP_D4{slash}MCU_TX1") (class "Default")
      (node (ref "U1") (pin "28") (pinfunction "PD3_TXD1/INT3_28") (pintype "bidirectional"))
      (node (ref "U4") (pin "45") (pinfunction "IO_L49N_D4_2_45") (pintype "bidirectional"))
    )
    (net (code "133") (name "SELECTMAP_D5{slash}MCU_RX1") (class "Default")
      (node (ref "U1") (pin "27") (pinfunction "PD2_RXD1/INT2_27") (pintype "bidirectional"))
      (node (ref "U4") (pin "44") (pinfunction "IO_L62P_D5_2_44") (pintype "bidirectional"))
    )
    (net (code "134") (name "SELECTMAP_D6{slash}SDA") (class "Default")
      (node (ref "R25") (pin "1") (pinfunction "1_1") (pintype "bidirectional"))
      (node (ref "U1") (pin "26") (pinfunction "PD1_SDA/INT1_26") (pintype "bidirectional"))
      (node (ref "U4") (pin "43") (pinfunction "IO_L62N_D6_2_43") (pintype "bidirectional"))
      (node (ref "U6") (pin "8") (pinfunction "SMDATA_8") (pintype "bidirectional"))
      (node (ref "U7") (pin "8") (pinfunction "SMDATA_8") (pintype "bidirectional"))
      (node (ref "U8") (pin "8") (pinfunction "SMDATA_8") (pintype "bidirectional"))
    )
    (net (code "135") (name "SELECTMAP_D7{slash}SCL") (class "Default")
      (node (ref "R24") (pin "1") (pinfunction "1_1") (pintype "bidirectional"))
      (node (ref "U1") (pin "25") (pinfunction "PD0_SCL/INT0_25") (pintype "bidirectional"))
      (node (ref "U4") (pin "48") (pinfunction "IO_L48P_D7_2_48") (pintype "bidirectional"))
      (node (ref "U6") (pin "9") (pinfunction "SMCLK_9") (pintype "bidirectional"))
      (node (ref "U7") (pin "9") (pinfunction "SMCLK_9") (pintype "bidirectional"))
      (node (ref "U8") (pin "9") (pinfunction "SMCLK_9") (pintype "bidirectional"))
    )
    (net (code "136") (name "SUSPEND") (class "Default")
      (node (ref "U4") (pin "73") (pinfunction "SUSPEND_73") (pintype "bidirectional"))
    )
    (net (code "137") (name "USB_SHIELD") (class "Default")
      (node (ref "J8") (pin "SHIELD1") (pinfunction "SHIELD_SHIELD1") (pintype "bidirectional"))
    )
    (net (code "138") (name "USB_VCC") (class "Default")
      (node (ref "C26") (pin "2") (pinfunction "P$2_2") (pintype "bidirectional"))
      (node (ref "C27") (pin "2") (pinfunction "P$2_2") (pintype "bidirectional"))
      (node (ref "L1") (pin "2") (pinfunction "P$2_2") (pintype "bidirectional"))
      (node (ref "R18") (pin "1") (pinfunction "1_1") (pintype "bidirectional"))
      (node (ref "U6") (pin "1") (pinfunction "SENSE1+_1") (pintype "bidirectional"))
    )
    (net (code "139") (name "USB_VCC_RAW") (class "Default")
      (node (ref "C25") (pin "1") (pinfunction "P$1_1") (pintype "bidirectional"))
      (node (ref "J8") (pin "1") (pinfunction "VCC_1") (pintype "bidirectional"))
      (node (ref "L1") (pin "1") (pinfunction "P$1_1") (pintype "bidirectional"))
    )
    (net (code "140") (name "WIRELESS_CS") (class "Default")
      (node (ref "R1") (pin "2") (pinfunction "2_2") (pintype "bidirectional"))
      (node (ref "U1") (pin "6") (pinfunction "PE4_OC3B/INT4_6") (pintype "bidirectional"))
      (node (ref "U3") (pin "8") (pinfunction "_CS_8") (pintype "bidirectional"))
    )
    (net (code "141") (name "WIRELESS_INT") (class "Default")
      (node (ref "U1") (pin "9") (pinfunction "PE7_ICP3/INT7_9") (pintype "bidirectional"))
      (node (ref "U3") (pin "4") (pinfunction "INT_4") (pintype "bidirectional"))
    )
    (net (code "142") (name "WIRELESS_RESET") (class "Default")
      (node (ref "U1") (pin "7") (pinfunction "PE5_OC3C/INT5_7") (pintype "bidirectional"))
      (node (ref "U3") (pin "2") (pinfunction "_RESET_2") (pintype "bidirectional"))
    )
    (net (code "143") (name "WIRELESS_VCC") (class "Default")
      (node (ref "R16") (pin "1") (pinfunction "1_1") (pintype "bidirectional"))
      (node (ref "U3") (pin "10") (pinfunction "VI_10") (pintype "bidirectional"))
      (node (ref "U6") (pin "4") (pinfunction "SENSE2-_4") (pintype "bidirectional"))
    )
    (net (code "144") (name "WIRELESS_WAKE") (class "Default")
      (node (ref "U1") (pin "8") (pinfunction "PE6_T3/INT6_8") (pintype "bidirectional"))
      (node (ref "U3") (pin "3") (pinfunction "WAKE_3") (pintype "bidirectional"))
    )
    (net (code "145") (name "WR") (class "Default")
      (node (ref "U1") (pin "33") (pinfunction "PG0_WR#_33") (pintype "bidirectional"))
      (node (ref "U4") (pin "74") (pinfunction "IO_L74N_DOUT_BUSY_1_74") (pintype "bidirectional"))
    )
    (net (code "146") (name "unconnected-(R25-Pad2)") (class "Default")
      (node (ref "R25") (pin "2") (pinfunction "2_2") (pintype "bidirectional"))
    )
    (net (code "147") (name "unconnected-(U1-_PEN-Pad1)") (class "Default")
      (node (ref "U1") (pin "1") (pinfunction "_PEN_1") (pintype "bidirectional"))
    )
    (net (code "148") (name "unconnected-(U4-CMPCS_B_2-Pad72)") (class "Default")
      (node (ref "U4") (pin "72") (pinfunction "CMPCS_B_2_72") (pintype "bidirectional"))
    )
    (net (code "149") (name "unconnected-(U4-IO_L2N_CMPMOSI_2-Pad66)") (class "Default")
      (node (ref "U4") (pin "66") (pinfunction "IO_L2N_CMPMOSI_2_66") (pintype "bidirectional"))
    )
    (net (code "150") (name "unconnected-(U4-IO_L2P_CMPCLK_2-Pad67)") (class "Default")
      (node (ref "U4") (pin "67") (pinfunction "IO_L2P_CMPCLK_2_67") (pintype "bidirectional"))
    )
    (net (code "151") (name "unconnected-(U4-IO_L3N_0-Pad139)") (class "Default")
      (node (ref "U4") (pin "139") (pinfunction "IO_L3N_0_139") (pintype "bidirectional"))
    )
    (net (code "152") (name "unconnected-(U4-IO_L4N_0-Pad137)") (class "Default")
      (node (ref "U4") (pin "137") (pinfunction "IO_L4N_0_137") (pintype "bidirectional"))
    )
    (net (code "153") (name "unconnected-(U4-IO_L4P_0-Pad138)") (class "Default")
      (node (ref "U4") (pin "138") (pinfunction "IO_L4P_0_138") (pintype "bidirectional"))
    )
    (net (code "154") (name "unconnected-(U4-IO_L30N_GCLK0_USERCCLK_2-Pad55)") (class "Default")
      (node (ref "U4") (pin "55") (pinfunction "IO_L30N_GCLK0_USERCCLK_2_55") (pintype "bidirectional"))
    )
    (net (code "155") (name "unconnected-(U4-IO_L34N_GCLK18_0-Pad133)") (class "Default")
      (node (ref "U4") (pin "133") (pinfunction "IO_L34N_GCLK18_0_133") (pintype "bidirectional"))
    )
    (net (code "156") (name "unconnected-(U4-IO_L34P_GCLK19_0-Pad134)") (class "Default")
      (node (ref "U4") (pin "134") (pinfunction "IO_L34P_GCLK19_0_134") (pintype "bidirectional"))
    )
    (net (code "157") (name "unconnected-(U4-IO_L35N_GCLK16_0-Pad131)") (class "Default")
      (node (ref "U4") (pin "131") (pinfunction "IO_L35N_GCLK16_0_131") (pintype "bidirectional"))
    )
    (net (code "158") (name "unconnected-(U4-IO_L35P_GCLK17_0-Pad132)") (class "Default")
      (node (ref "U4") (pin "132") (pinfunction "IO_L35P_GCLK17_0_132") (pintype "bidirectional"))
    )
    (net (code "159") (name "unconnected-(U4-IO_L36N_GCLK14_0-Pad126)") (class "Default")
      (node (ref "U4") (pin "126") (pinfunction "IO_L36N_GCLK14_0_126") (pintype "bidirectional"))
    )
    (net (code "160") (name "unconnected-(U4-IO_L36P_GCLK15_0-Pad127)") (class "Default")
      (node (ref "U4") (pin "127") (pinfunction "IO_L36P_GCLK15_0_127") (pintype "bidirectional"))
    )
    (net (code "161") (name "unconnected-(U4-IO_L37N_GCLK12_0-Pad123)") (class "Default")
      (node (ref "U4") (pin "123") (pinfunction "IO_L37N_GCLK12_0_123") (pintype "bidirectional"))
    )
    (net (code "162") (name "unconnected-(U4-IO_L37P_GCLK13_0-Pad124)") (class "Default")
      (node (ref "U4") (pin "124") (pinfunction "IO_L37P_GCLK13_0_124") (pintype "bidirectional"))
    )
    (net (code "163") (name "unconnected-(U4-IO_L42N_GCLK24_3-Pad21)") (class "Default")
      (node (ref "U4") (pin "21") (pinfunction "IO_L42N_GCLK24_3_21") (pintype "bidirectional"))
    )
    (net (code "164") (name "unconnected-(U4-IO_L42P_GCLK25_TRDY2_3-Pad22)") (class "Default")
      (node (ref "U4") (pin "22") (pinfunction "IO_L42P_GCLK25_TRDY2_3_22") (pintype "bidirectional"))
    )
    (net (code "165") (name "unconnected-(U4-IO_L43N_GCLK22_IRDY2_3-Pad16)") (class "Default")
      (node (ref "U4") (pin "16") (pinfunction "IO_L43N_GCLK22_IRDY2_3_16") (pintype "bidirectional"))
    )
    (net (code "166") (name "unconnected-(U4-IO_L43P_GCLK23_3-Pad17)") (class "Default")
      (node (ref "U4") (pin "17") (pinfunction "IO_L43P_GCLK23_3_17") (pintype "bidirectional"))
    )
    (net (code "167") (name "unconnected-(U4-IO_L44N_GCLK20_3-Pad14)") (class "Default")
      (node (ref "U4") (pin "14") (pinfunction "IO_L44N_GCLK20_3_14") (pintype "bidirectional"))
    )
    (net (code "168") (name "unconnected-(U4-IO_L44P_GCLK21_3-Pad15)") (class "Default")
      (node (ref "U4") (pin "15") (pinfunction "IO_L44P_GCLK21_3_15") (pintype "bidirectional"))
    )
    (net (code "169") (name "unconnected-(U4-IO_L62N_VREF_0-Pad120)") (class "Default")
      (node (ref "U4") (pin "120") (pinfunction "IO_L62N_VREF_0_120") (pintype "bidirectional"))
    )
    (net (code "170") (name "unconnected-(U4-IO_L62P_0-Pad121)") (class "Default")
      (node (ref "U4") (pin "121") (pinfunction "IO_L62P_0_121") (pintype "bidirectional"))
    )
    (net (code "171") (name "unconnected-(U4-IO_L63N_SCP6_0-Pad118)") (class "Default")
      (node (ref "U4") (pin "118") (pinfunction "IO_L63N_SCP6_0_118") (pintype "bidirectional"))
    )
    (net (code "172") (name "unconnected-(U4-IO_L63P_SCP7_0-Pad119)") (class "Default")
      (node (ref "U4") (pin "119") (pinfunction "IO_L63P_SCP7_0_119") (pintype "bidirectional"))
    )
    (net (code "173") (name "unconnected-(U4-IO_L64N_SCP4_0-Pad116)") (class "Default")
      (node (ref "U4") (pin "116") (pinfunction "IO_L64N_SCP4_0_116") (pintype "bidirectional"))
    )
    (net (code "174") (name "unconnected-(U4-IO_L64P_SCP5_0-Pad117)") (class "Default")
      (node (ref "U4") (pin "117") (pinfunction "IO_L64P_SCP5_0_117") (pintype "bidirectional"))
    )
    (net (code "175") (name "unconnected-(U4-IO_L65N_SCP2_0-Pad114)") (class "Default")
      (node (ref "U4") (pin "114") (pinfunction "IO_L65N_SCP2_0_114") (pintype "bidirectional"))
    )
    (net (code "176") (name "unconnected-(U4-IO_L65P_SCP3_0-Pad115)") (class "Default")
      (node (ref "U4") (pin "115") (pinfunction "IO_L65P_SCP3_0_115") (pintype "bidirectional"))
    )
    (net (code "177") (name "unconnected-(U4-IO_L66N_SCP0_0-Pad111)") (class "Default")
      (node (ref "U4") (pin "111") (pinfunction "IO_L66N_SCP0_0_111") (pintype "bidirectional"))
    )
    (net (code "178") (name "unconnected-(U4-IO_L66P_SCP1_0-Pad112)") (class "Default")
      (node (ref "U4") (pin "112") (pinfunction "IO_L66P_SCP1_0_112") (pintype "bidirectional"))
    )
    (net (code "179") (name "unconnected-(U6-ALERT#-Pad7)") (class "Default")
      (node (ref "U6") (pin "7") (pinfunction "ALERT#_7") (pintype "bidirectional"))
    )
    (net (code "180") (name "unconnected-(U7-ALERT#-Pad7)") (class "Default")
      (node (ref "U7") (pin "7") (pinfunction "ALERT#_7") (pintype "bidirectional"))
    )
    (net (code "181") (name "unconnected-(U8-ALERT#-Pad7)") (class "Default")
      (node (ref "U8") (pin "7") (pinfunction "ALERT#_7") (pintype "bidirectional"))
    )
    (net (code "182") (name "unconnected-(U8-SENSE1+-Pad1)") (class "Default")
      (node (ref "U8") (pin "1") (pinfunction "SENSE1+_1") (pintype "bidirectional"))
    )
    (net (code "183") (name "unconnected-(U8-SENSE1--Pad2)") (class "Default")
      (node (ref "U8") (pin "2") (pinfunction "SENSE1-_2") (pintype "bidirectional"))
    )
    (net (code "184") (name "unconnected-(U9-CBUS1-Pad21)") (class "Default")
      (node (ref "U9") (pin "21") (pinfunction "CBUS1_21") (pintype "bidirectional"))
    )
  )
)
